# SELFiSSH.net
KiCad netlist of a schematic drawn in EAGLE
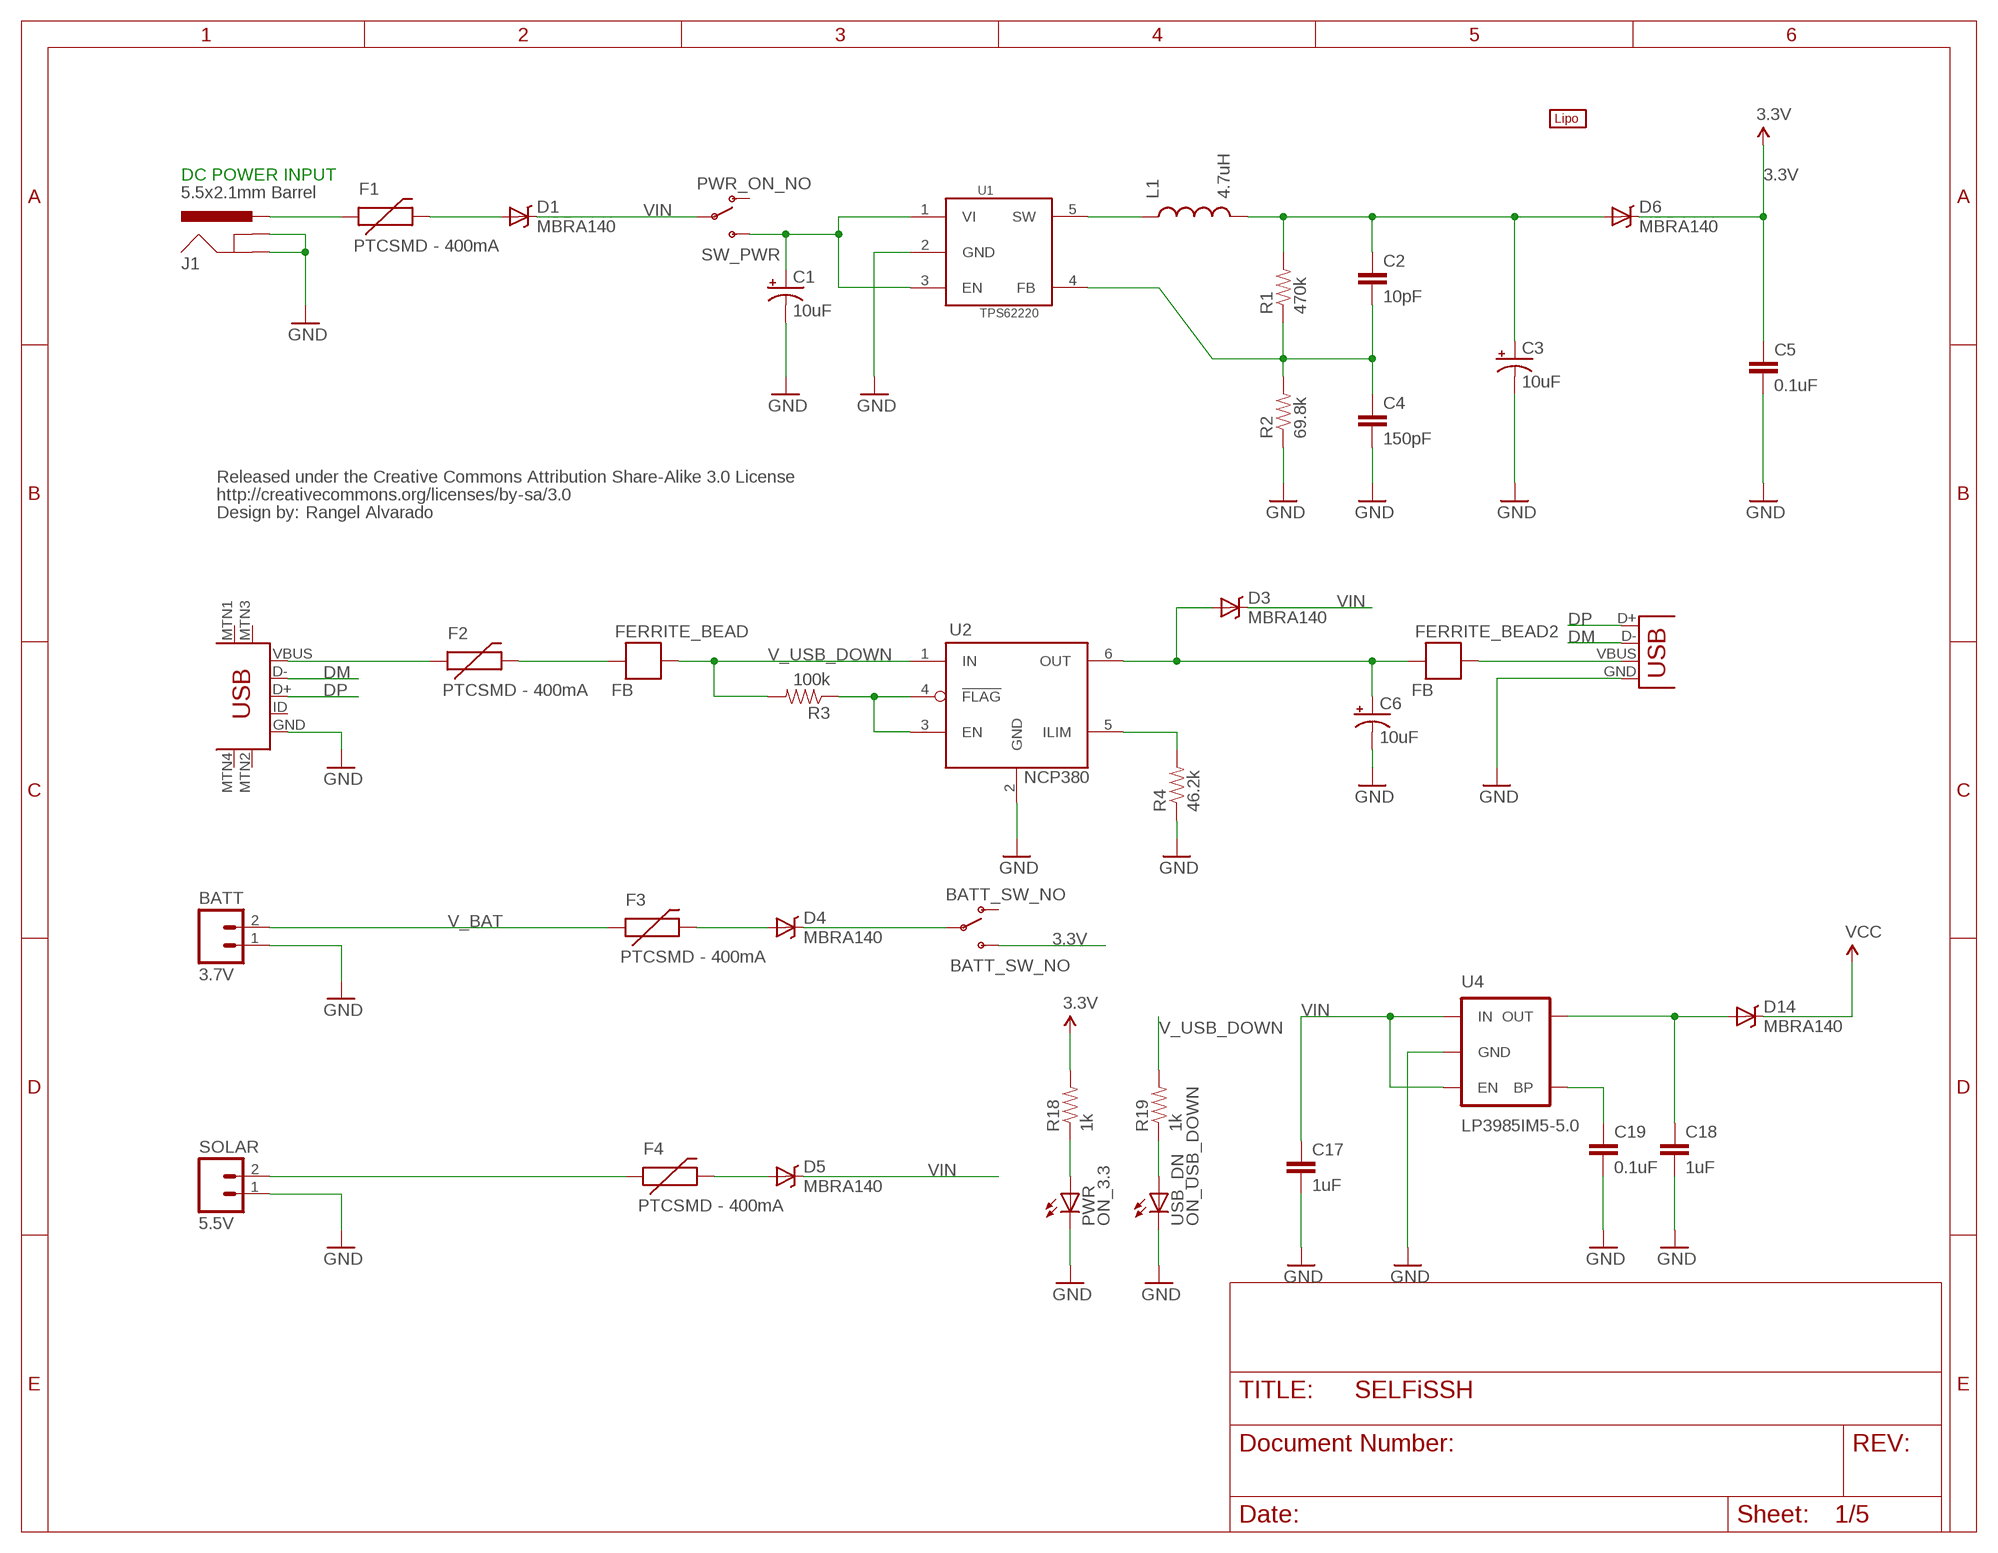
[diagram p0: schematic, sheet 1]
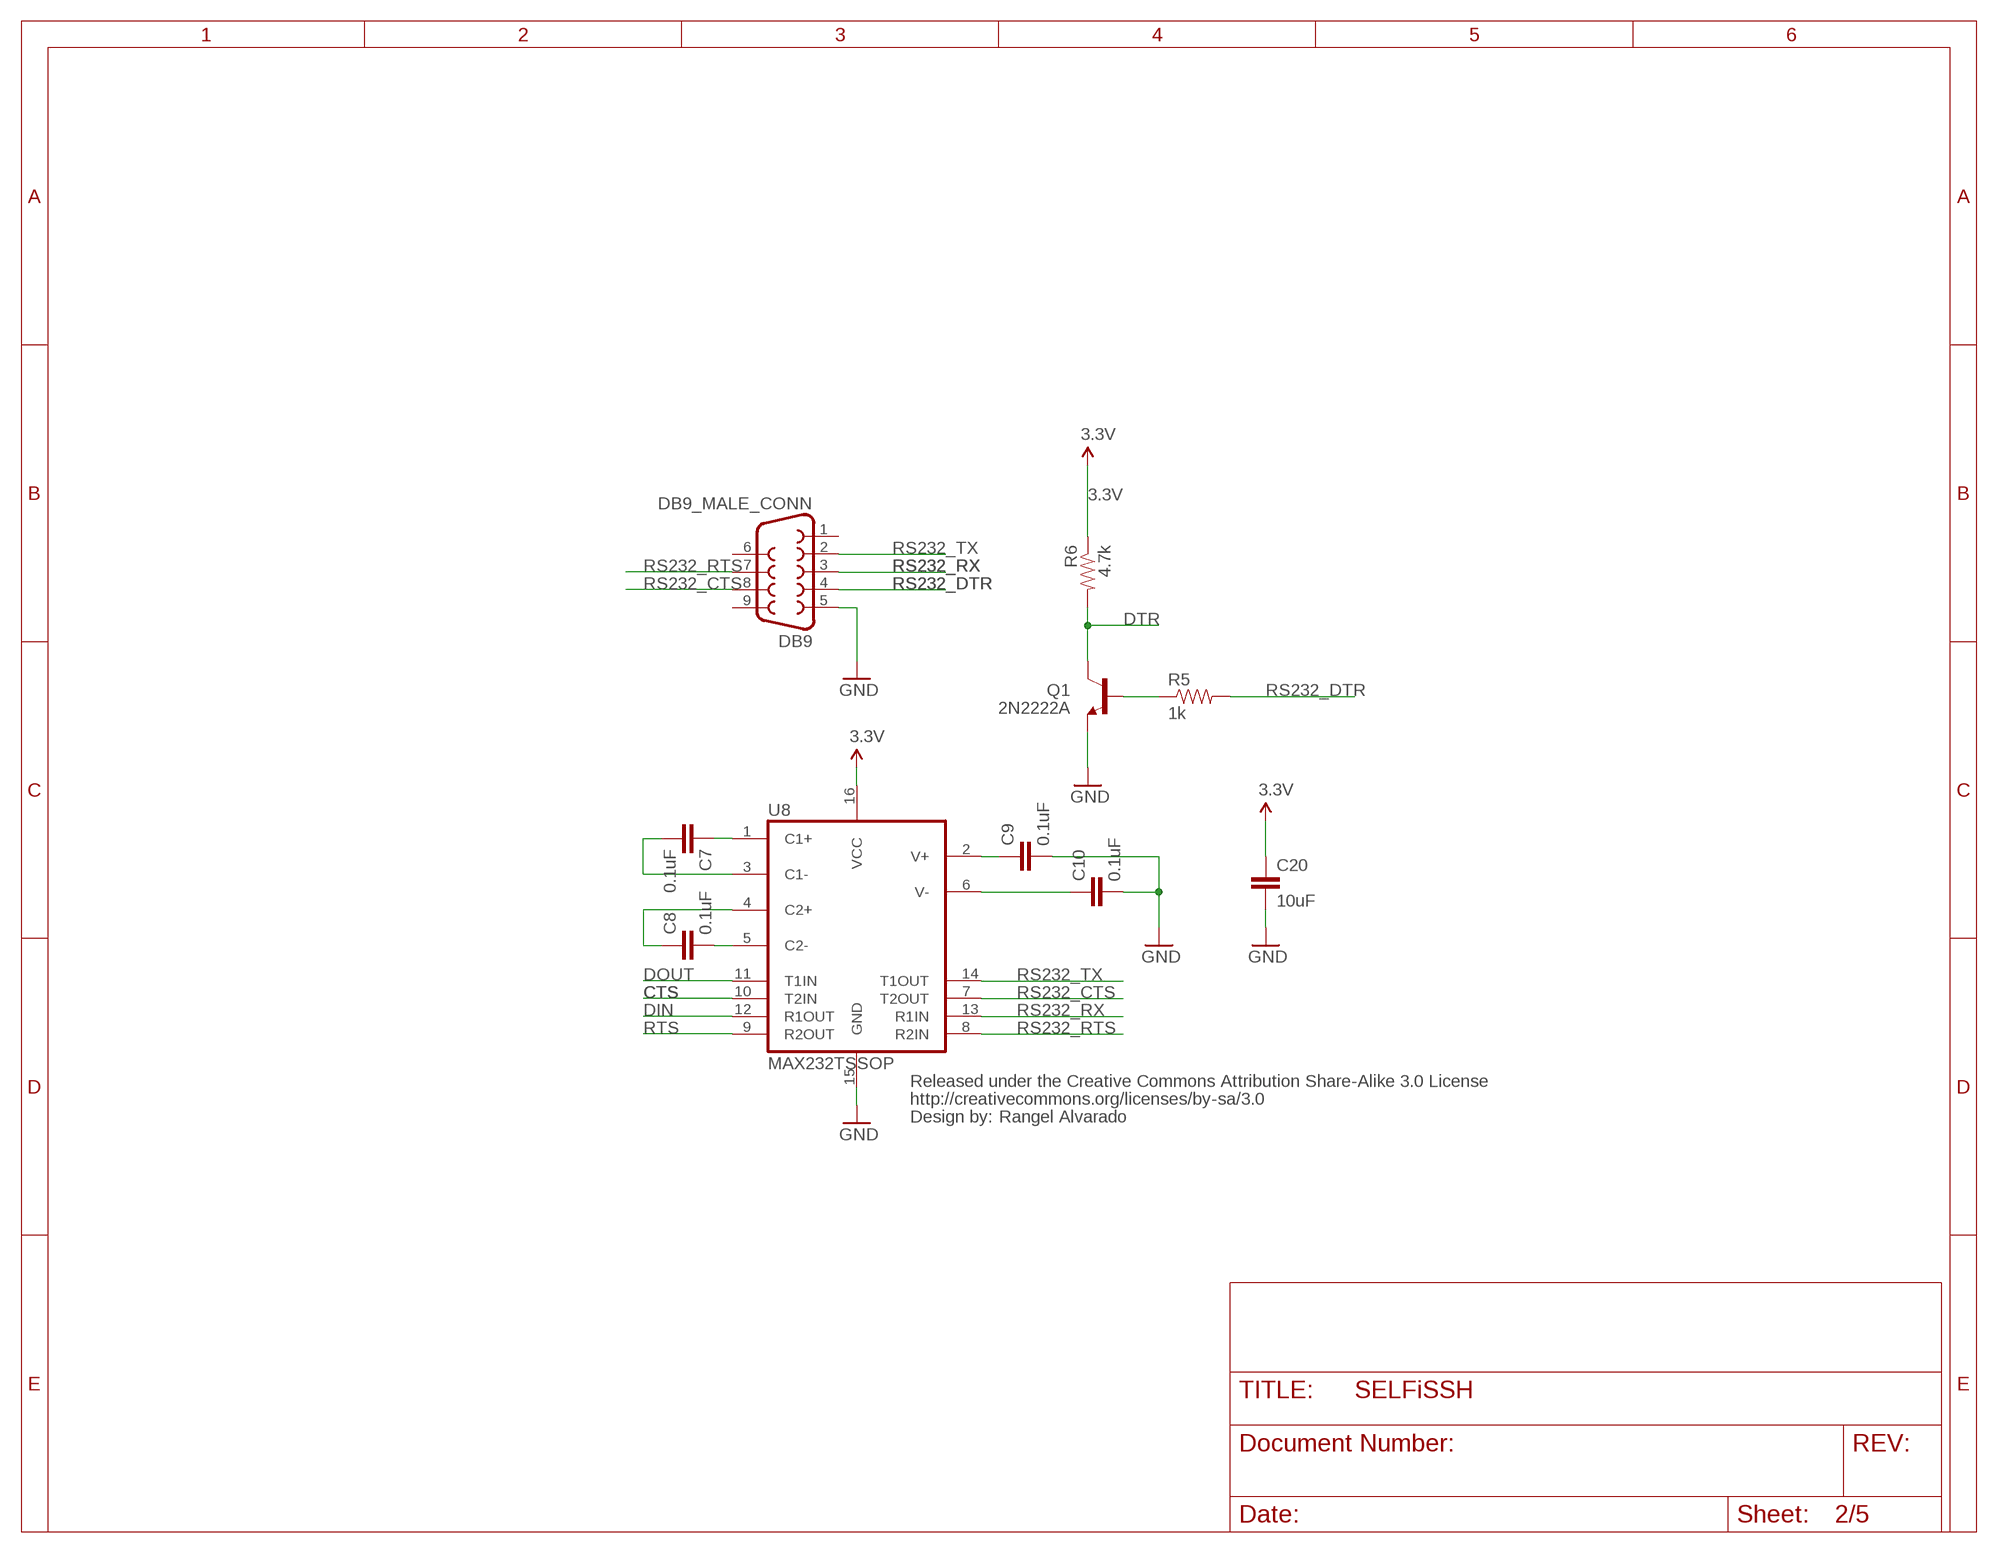
[diagram p1: schematic, sheet 2]
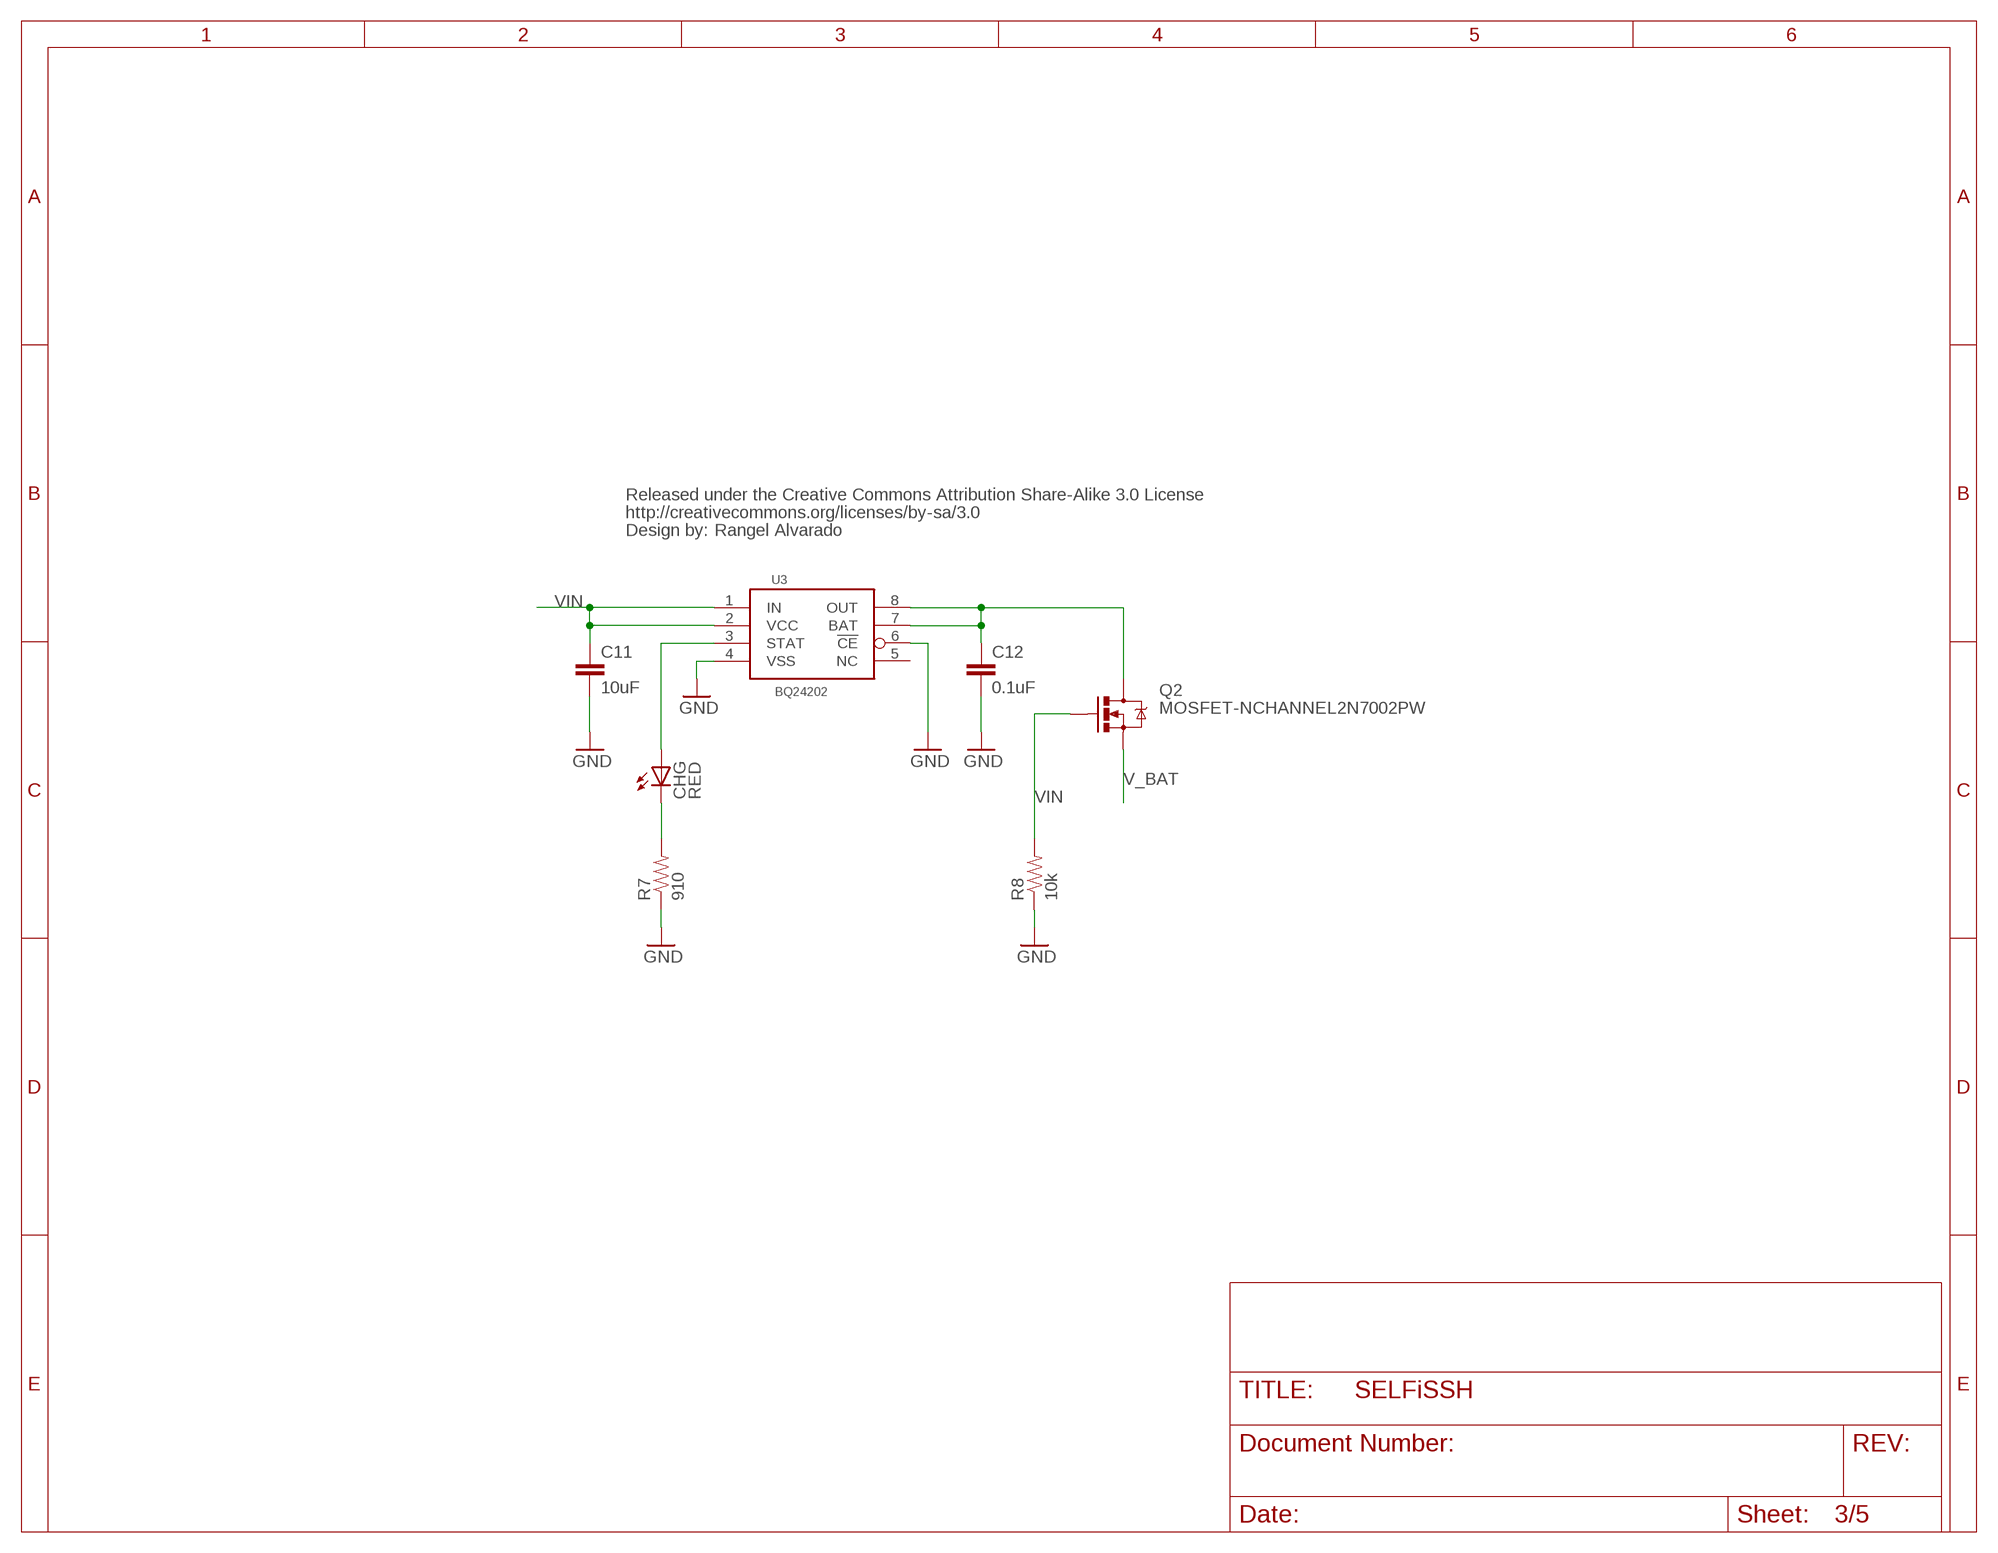
[diagram p2: schematic, sheet 3]
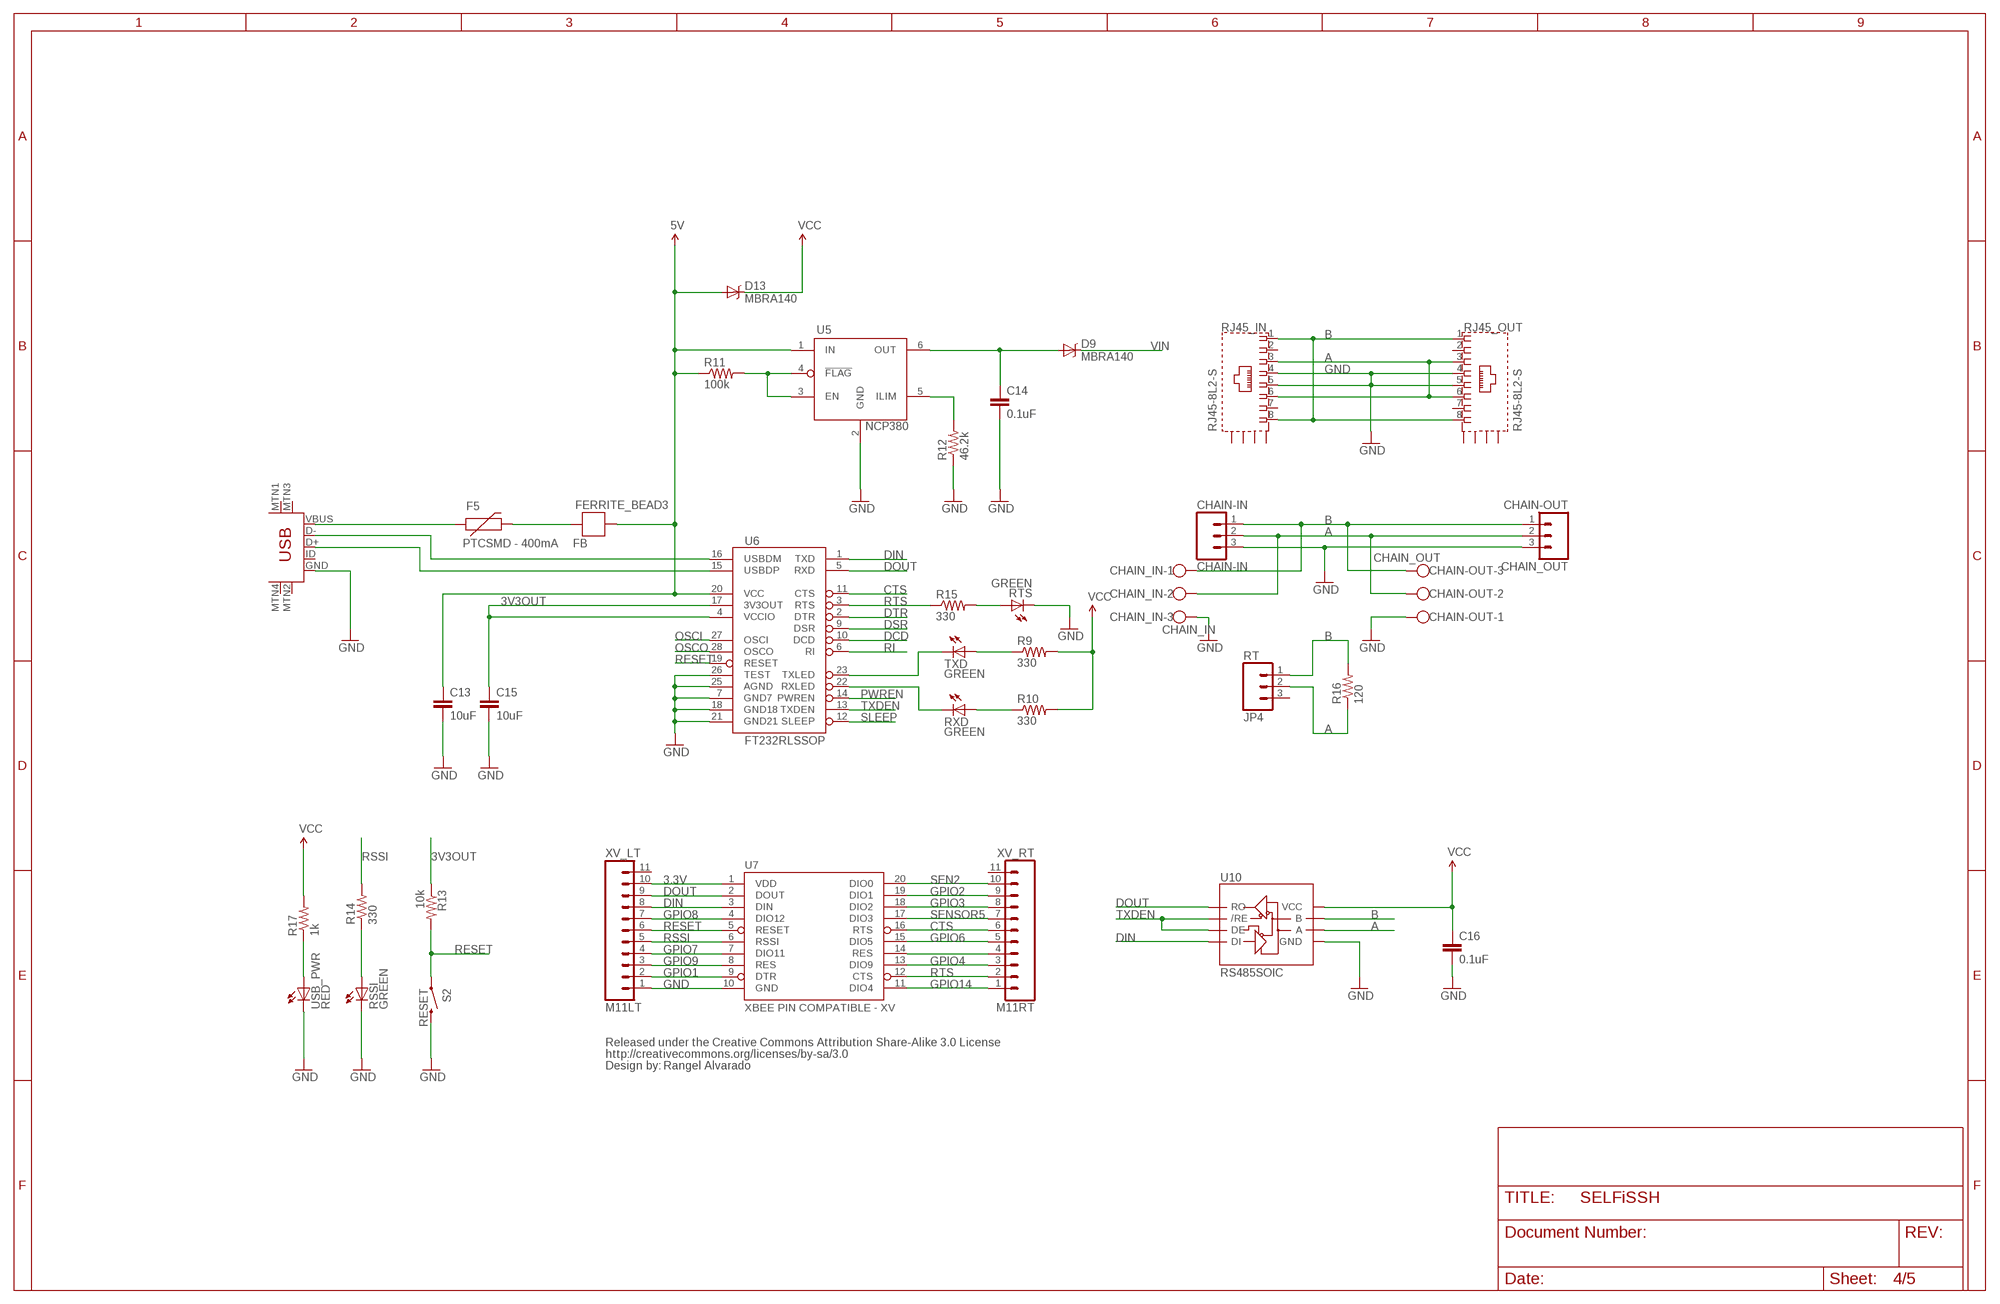
[diagram p3: schematic, sheet 4]
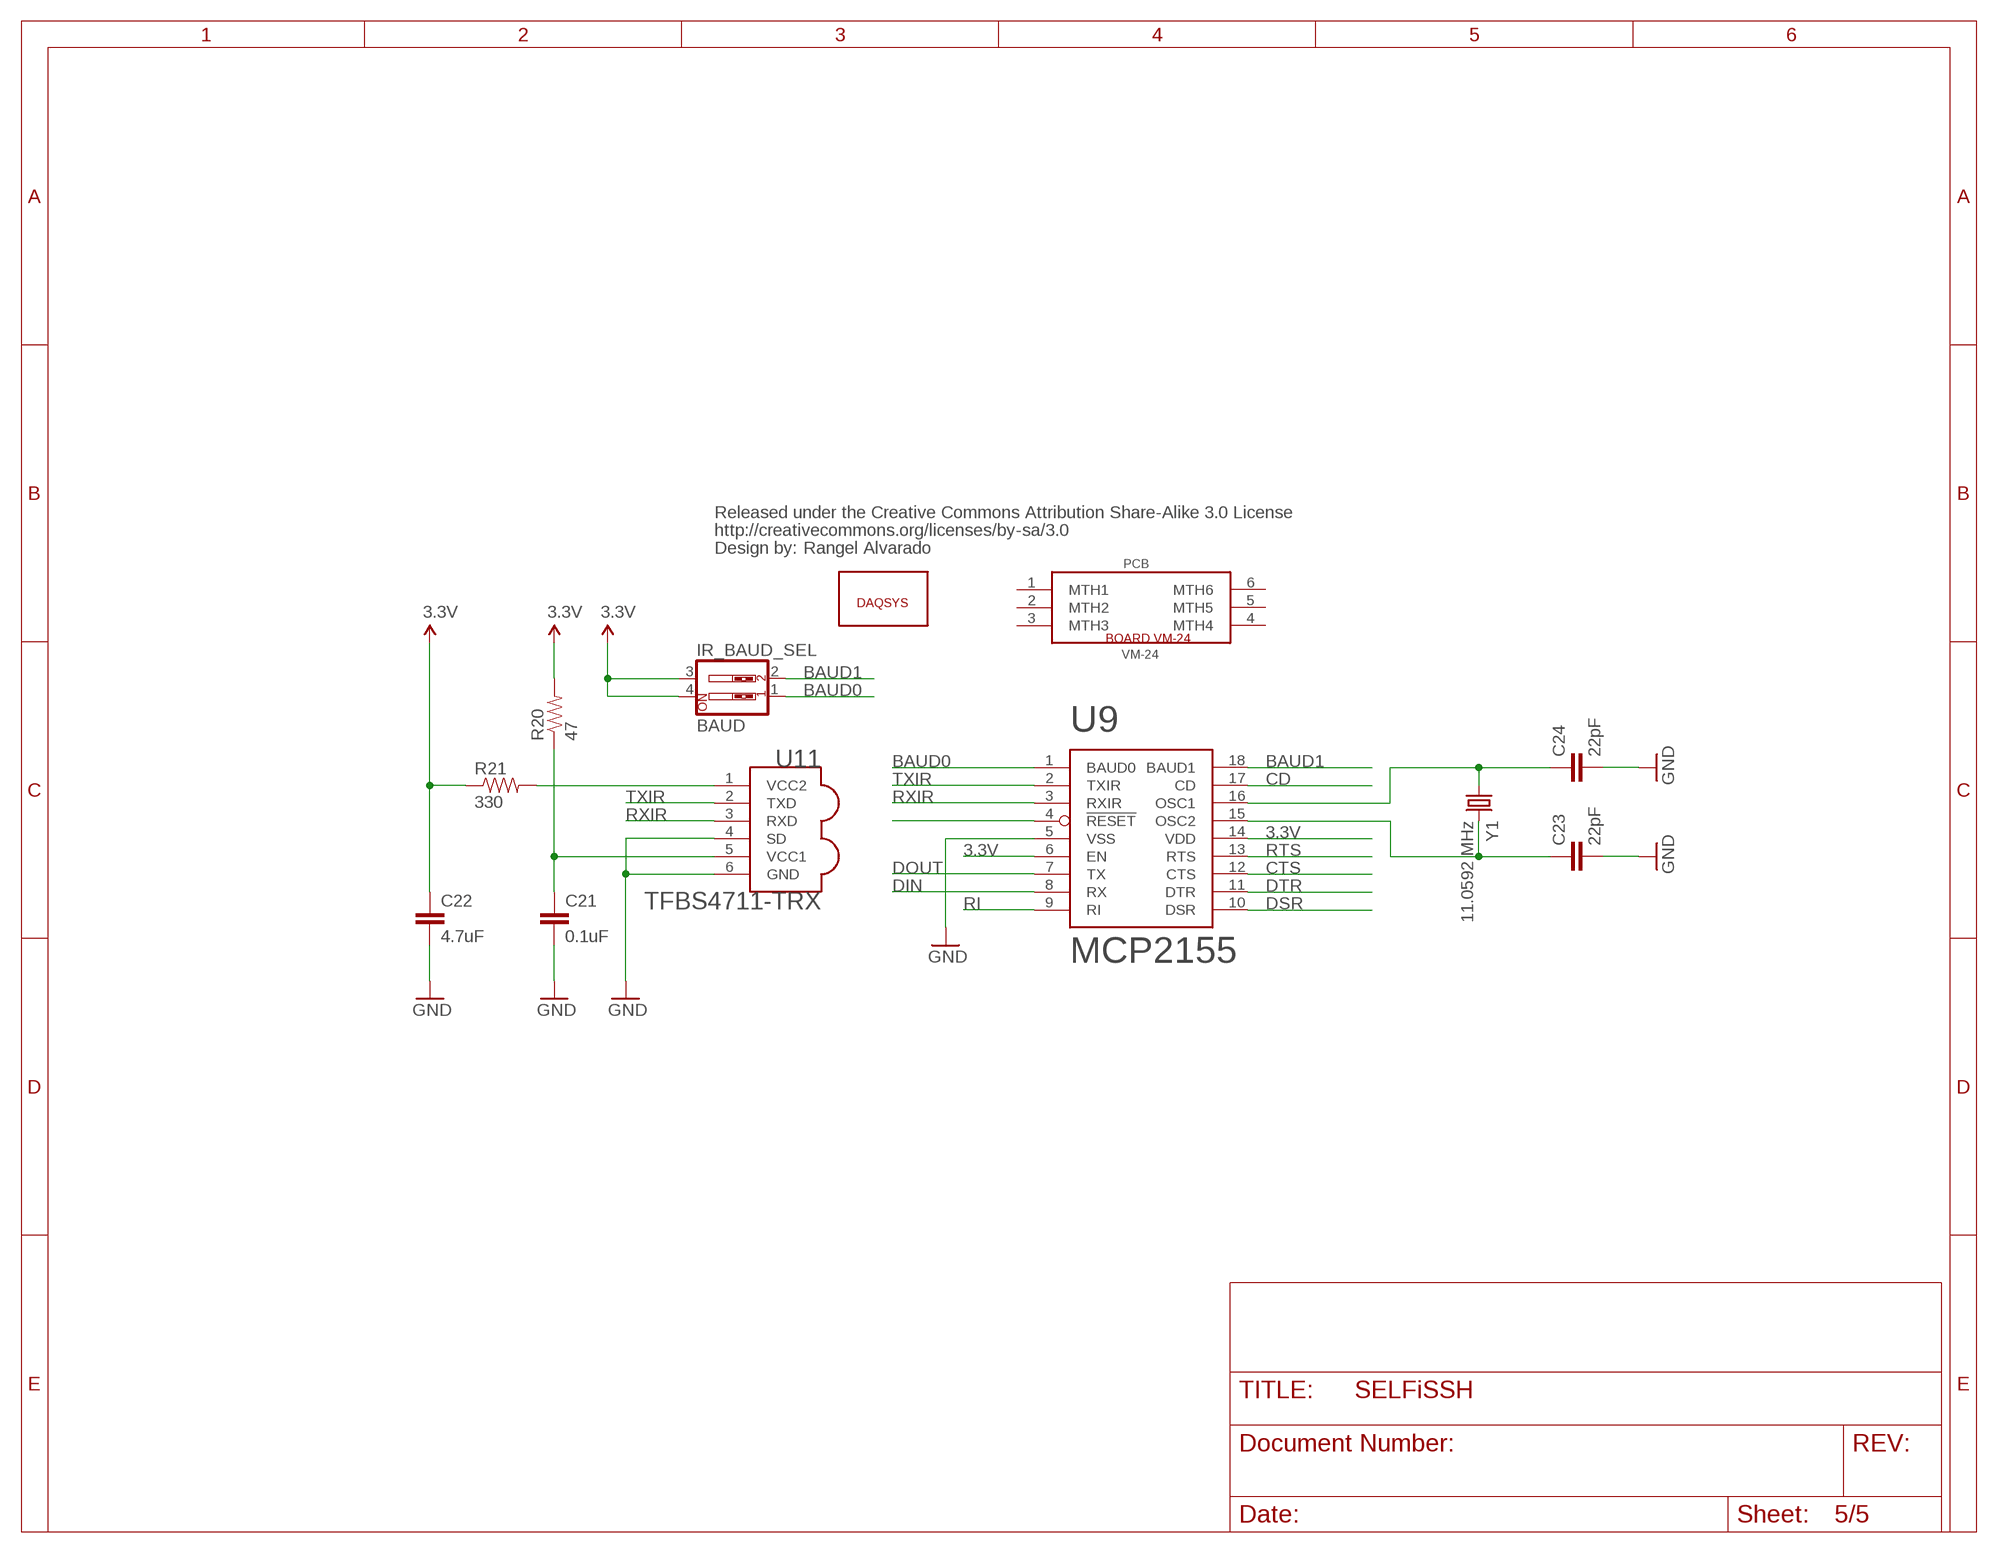
[diagram p4: schematic, sheet 5]

(export (version "E")
  (design (tool "Eeschema 10.0.6"))
  (components
    (comp (ref "C11")
      (value "10uF")
      (footprint "eagle-import:0805")
      (libsource (lib "eagle-import") (part "CAP0805"))
    )
    (comp (ref "C12")
      (value "0.1uF")
      (footprint "eagle-import:0805")
      (libsource (lib "eagle-import") (part "CAP0805"))
    )
    (comp (ref "CC_TEXT3")
      (value "CREATIVE_COMMONS")
      (footprint "eagle-import:CREATIVE_COMMONS")
      (libsource (lib "eagle-import") (part "CREATIVE_COMMONS"))
    )
    (comp (ref "CHG")
      (value "RED")
      (footprint "eagle-import:LED-1206")
      (libsource (lib "eagle-import") (part "LED-RED1206"))
    )
    (comp (ref "Q2")
      (value "MOSFET-NCHANNEL2N7002PW")
      (footprint "eagle-import:SOT323")
      (libsource (lib "eagle-import") (part "MOSFET-NCHANNEL2N7002PW"))
    )
    (comp (ref "R7")
      (value "910")
      (footprint "eagle-import:0805")
      (libsource (lib "eagle-import") (part "SparkFun-Resistors_RESISTOR0805-RES"))
    )
    (comp (ref "R8")
      (value "10k")
      (footprint "eagle-import:0805")
      (libsource (lib "eagle-import") (part "SparkFun-Resistors_RESISTOR0805-RES"))
    )
    (comp (ref "U3")
      (value "BQ24202")
      (footprint "eagle-import:MSOP-8")
      (libsource (lib "eagle-import") (part "BQ24202"))
    )
    (comp (ref "C7")
      (value "0.1uF")
      (footprint "eagle-import:0402-CAP")
      (libsource (lib "eagle-import") (part ".1UF-CER"))
    )
    (comp (ref "C8")
      (value "0.1uF")
      (footprint "eagle-import:0402-CAP")
      (libsource (lib "eagle-import") (part ".1UF-CER"))
    )
    (comp (ref "C9")
      (value "0.1uF")
      (footprint "eagle-import:0402-CAP")
      (libsource (lib "eagle-import") (part ".1UF-CER"))
    )
    (comp (ref "C10")
      (value "0.1uF")
      (footprint "eagle-import:0402-CAP")
      (libsource (lib "eagle-import") (part ".1UF-CER"))
    )
    (comp (ref "C20")
      (value "10uF")
      (footprint "eagle-import:0402-CAP")
      (libsource (lib "eagle-import") (part ".1UF-CER"))
    )
    (comp (ref "CC_TEXT2")
      (value "CREATIVE_COMMONS")
      (footprint "eagle-import:CREATIVE_COMMONS")
      (libsource (lib "eagle-import") (part "CREATIVE_COMMONS"))
    )
    (comp (ref "DB9_MALE_CONN")
      (value "DB9")
      (footprint "eagle-import:F09HP")
      (libsource (lib "eagle-import") (part "F09HP"))
    )
    (comp (ref "Q1")
      (value "2N2222A")
      (footprint "eagle-import:SOT23-3")
      (libsource (lib "eagle-import") (part "TRANSISTOR_NPNSOT23-3"))
    )
    (comp (ref "R5")
      (value "1k")
      (footprint "eagle-import:0402-RES")
      (libsource (lib "eagle-import") (part "RESISTOR0402-RES"))
    )
    (comp (ref "R6")
      (value "4.7k")
      (footprint "eagle-import:0402-RES")
      (libsource (lib "eagle-import") (part "RESISTOR0402-RES"))
    )
    (comp (ref "U8")
      (value "MAX232TSSOP")
      (footprint "eagle-import:TSSOP16")
      (libsource (lib "eagle-import") (part "MAX232TSSOP"))
    )
    (comp (ref "C13")
      (value "10uF")
      (footprint "eagle-import:0805")
      (libsource (lib "eagle-import") (part "CAP0805"))
    )
    (comp (ref "C14")
      (value "0.1uF")
      (footprint "eagle-import:0805")
      (libsource (lib "eagle-import") (part "CAP0805"))
    )
    (comp (ref "C15")
      (value "10uF")
      (footprint "eagle-import:0805")
      (libsource (lib "eagle-import") (part "CAP0805"))
    )
    (comp (ref "C16")
      (value "0.1uF")
      (footprint "eagle-import:0805")
      (libsource (lib "eagle-import") (part "CAP0805"))
    )
    (comp (ref "CC_TEXT4")
      (value "CREATIVE_COMMONS")
      (footprint "eagle-import:CREATIVE_COMMONS")
      (libsource (lib "eagle-import") (part "CREATIVE_COMMONS"))
    )
    (comp (ref "CHAIN-IN")
      (value "CHAIN-IN")
      (footprint "eagle-import:1X03_LONGPADS")
      (libsource (lib "eagle-import") (part "M03LONGPADS"))
    )
    (comp (ref "CHAIN-OUT")
      (value "CHAIN_OUT")
      (footprint "eagle-import:W237-103")
      (fields (field (name "MPN") "237-103"))
      (libsource (lib "eagle-import") (part "W237-103"))
    )
    (comp (ref "CHAIN_IN")
      (value "CHAIN_IN")
      (footprint "eagle-import:W237-103")
      (fields (field (name "MPN") "237-103"))
      (libsource (lib "eagle-import") (part "W237-103"))
    )
    (comp (ref "CHAIN_OUT")
      (value "CHAIN-OUT")
      (footprint "eagle-import:1X03_LONGPADS")
      (libsource (lib "eagle-import") (part "M03LONGPADS"))
    )
    (comp (ref "D9")
      (value "MBRA140")
      (footprint "eagle-import:SMA-DIODE")
      (libsource (lib "eagle-import") (part "MBRA140"))
    )
    (comp (ref "D13")
      (value "MBRA140")
      (footprint "eagle-import:SMA-DIODE")
      (fields (field (name "PROD_ID") "DIO-08053"))
      (libsource (lib "eagle-import") (part "MBRA140"))
    )
    (comp (ref "F5")
      (value "PTCSMD - 400mA")
      (footprint "eagle-import:PTC-1206")
      (libsource (lib "eagle-import") (part "PTCSMD"))
    )
    (comp (ref "FERRITE_BEAD3")
      (value "FB")
      (footprint "eagle-import:0603")
      (libsource (lib "eagle-import") (part "FB"))
    )
    (comp (ref "FTDI")
      (value "FTDI")
      (footprint "eagle-import:USB-MINIB")
      (libsource (lib "eagle-import") (part "USB-MINIB-5PIN"))
    )
    (comp (ref "JP4")
      (value "RT")
      (footprint "eagle-import:1X03_LONGPADS")
      (libsource (lib "eagle-import") (part "M03LONGPADS"))
    )
    (comp (ref "R9")
      (value "330")
      (footprint "eagle-import:0805")
      (libsource (lib "eagle-import") (part "RESISTOR0805-RES"))
    )
    (comp (ref "R10")
      (value "330")
      (footprint "eagle-import:0805")
      (libsource (lib "eagle-import") (part "RESISTOR0805-RES"))
    )
    (comp (ref "R11")
      (value "100k")
      (footprint "eagle-import:0805")
      (libsource (lib "eagle-import") (part "RESISTOR0805-RES"))
    )
    (comp (ref "R12")
      (value "46.2k")
      (footprint "eagle-import:0805")
      (libsource (lib "eagle-import") (part "RESISTOR0805-RES"))
    )
    (comp (ref "R13")
      (value "10k")
      (footprint "eagle-import:0805")
      (libsource (lib "eagle-import") (part "RESISTOR0805-RES"))
    )
    (comp (ref "R14")
      (value "330")
      (footprint "eagle-import:0805")
      (libsource (lib "eagle-import") (part "RESISTOR0805-RES"))
    )
    (comp (ref "R15")
      (value "330")
      (footprint "eagle-import:0805")
      (libsource (lib "eagle-import") (part "RESISTOR0805-RES"))
    )
    (comp (ref "R16")
      (value "120")
      (footprint "eagle-import:0805")
      (libsource (lib "eagle-import") (part "RESISTOR0805-RES"))
    )
    (comp (ref "R17")
      (value "1k")
      (footprint "eagle-import:0805")
      (libsource (lib "eagle-import") (part "RESISTOR0805-RES"))
    )
    (comp (ref "RJ45_IN")
      (value "RJ45-8L2-S")
      (footprint "eagle-import:RJ45-SHIELD2")
      (fields (field (name "MF") "TYCO ELECTRONICS"))
      (libsource (lib "eagle-import") (part "RJ452-S-8L"))
    )
    (comp (ref "RJ45_OUT")
      (value "RJ45-8L2-S")
      (footprint "eagle-import:RJ45-SHIELD2")
      (fields (field (name "MF") "TYCO ELECTRONICS"))
      (libsource (lib "eagle-import") (part "RJ452-S-8L"))
    )
    (comp (ref "RSSI")
      (value "GREEN")
      (footprint "eagle-import:LED-0603")
      (libsource (lib "eagle-import") (part "LED-GREEN0603"))
    )
    (comp (ref "RTS")
      (value "GREEN")
      (footprint "eagle-import:LED-0603")
      (libsource (lib "eagle-import") (part "LED0603"))
    )
    (comp (ref "RXD")
      (value "GREEN")
      (footprint "eagle-import:LED-0603")
      (libsource (lib "eagle-import") (part "LED0603"))
    )
    (comp (ref "S2")
      (value "RESET")
      (footprint "eagle-import:TACTILE_SWITCH_TALL")
      (libsource (lib "eagle-import") (part "SWITCH-MOMENTARY-2"))
    )
    (comp (ref "TXD")
      (value "GREEN")
      (footprint "eagle-import:LED-0603")
      (libsource (lib "eagle-import") (part "LED0603"))
    )
    (comp (ref "U5")
      (value "NCP380")
      (footprint "eagle-import:TSOP6")
      (libsource (lib "eagle-import") (part "NCP380NCP380VCC5"))
    )
    (comp (ref "U6")
      (value "FT232RLSSOP")
      (footprint "eagle-import:SSOP28DB")
      (libsource (lib "eagle-import") (part "FT232RLSSOP"))
    )
    (comp (ref "U7")
      (value "XBEE PIN COMPATIBLE - XV")
      (footprint "eagle-import:XBEE-SMD")
      (libsource (lib "eagle-import") (part "XBEE-1B3"))
    )
    (comp (ref "U10")
      (value "RS485SOIC")
      (footprint "eagle-import:SO08")
      (libsource (lib "eagle-import") (part "RS485SOIC"))
    )
    (comp (ref "USB_PWR")
      (value "RED")
      (footprint "eagle-import:LED-1206")
      (libsource (lib "eagle-import") (part "LED1206"))
    )
    (comp (ref "XV_LT")
      (value "M11LT")
      (footprint "eagle-import:1X11_LONGPADS")
      (libsource (lib "eagle-import") (part "M11LONGPADS"))
    )
    (comp (ref "XV_RT")
      (value "M11RT")
      (footprint "eagle-import:1X11_LONGPADS")
      (libsource (lib "eagle-import") (part "M11LONGPADS"))
    )
    (comp (ref "C21")
      (value "0.1uF")
      (footprint "eagle-import:0603-CAP")
      (libsource (lib "eagle-import") (part "CAP0603-CAP"))
    )
    (comp (ref "C22")
      (value "4.7uF")
      (footprint "eagle-import:0603-CAP")
      (libsource (lib "eagle-import") (part "CAP0603-CAP"))
    )
    (comp (ref "C23")
      (value "22pF")
      (footprint "eagle-import:0603-CAP")
      (libsource (lib "eagle-import") (part "CAP0603-CAP"))
    )
    (comp (ref "C24")
      (value "22pF")
      (footprint "eagle-import:0603-CAP")
      (libsource (lib "eagle-import") (part "CAP0603-CAP"))
    )
    (comp (ref "CC_TEXT5")
      (value "CREATIVE_COMMONS")
      (footprint "eagle-import:CREATIVE_COMMONS")
      (libsource (lib "eagle-import") (part "CREATIVE_COMMONS"))
    )
    (comp (ref "IR_BAUD_SEL")
      (value "BAUD")
      (footprint "eagle-import:DIPSWITCH-02")
      (libsource (lib "eagle-import") (part "SW_DIP-2"))
    )
    (comp (ref "PCB")
      (value "VM-24")
      (footprint "eagle-import:VM-24")
      (libsource (lib "eagle-import") (part "VM-24"))
    )
    (comp (ref "R20")
      (value "47")
      (footprint "eagle-import:0603-RES")
      (libsource (lib "eagle-import") (part "SparkFun-Resistors_RESISTOR0603-RES"))
    )
    (comp (ref "R21")
      (value "330")
      (footprint "eagle-import:0603-RES")
      (libsource (lib "eagle-import") (part "SparkFun-Resistors_RESISTOR0603-RES"))
    )
    (comp (ref "U$1")
      (value "DAQSYS")
      (footprint "eagle-import:DAQSYS")
      (libsource (lib "eagle-import") (part "DAQSYS"))
    )
    (comp (ref "U9")
      (value "MCP2155")
      (footprint "eagle-import:SOIC18-W")
      (libsource (lib "eagle-import") (part "MCP2155"))
    )
    (comp (ref "U11")
      (value "TFBS4711-TRX")
      (footprint "eagle-import:SMD-6")
      (libsource (lib "eagle-import") (part "TFBS4711-TRX"))
    )
    (comp (ref "Y1")
      (value "11.0592 MHz")
      (footprint "eagle-import:CRYSTAL-SMD-5X3")
      (libsource (lib "eagle-import") (part "CRYSTAL5X3"))
    )
    (comp (ref "BATT")
      (value "3.7V")
      (footprint "eagle-import:JST-2-PTH")
      (libsource (lib "eagle-import") (part "M02JST-PTH-2"))
    )
    (comp (ref "BATT_SW_NO")
      (value "BATT_SW_NO")
      (footprint "eagle-import:SWITCH-SPDT-SMD")
      (libsource (lib "eagle-import") (part "SWITCH-SPDTSMD2"))
    )
    (comp (ref "C1")
      (value "10uF")
      (footprint "eagle-import:EIA3216")
      (libsource (lib "eagle-import") (part "10UF-16V-10%(TANT)"))
    )
    (comp (ref "C2")
      (value "10pF")
      (footprint "eagle-import:0805")
      (libsource (lib "eagle-import") (part "1UF-25V-10%(0805)"))
    )
    (comp (ref "C3")
      (value "10uF")
      (footprint "eagle-import:EIA3216")
      (libsource (lib "eagle-import") (part "10UF-16V-10%(TANT)"))
    )
    (comp (ref "C4")
      (value "150pF")
      (footprint "eagle-import:0805")
      (libsource (lib "eagle-import") (part "1UF-25V-10%(0805)"))
    )
    (comp (ref "C5")
      (value "0.1uF")
      (footprint "eagle-import:0805")
      (libsource (lib "eagle-import") (part "1UF-25V-10%(0805)"))
    )
    (comp (ref "C6")
      (value "10uF")
      (footprint "eagle-import:EIA3216")
      (libsource (lib "eagle-import") (part "10UF-16V-10%(TANT)"))
    )
    (comp (ref "C17")
      (value "1uF")
      (footprint "eagle-import:0805")
      (fields (field (name "PROD_ID") "CAP-08064"))
      (libsource (lib "eagle-import") (part "1UF-25V-10%(0805)"))
    )
    (comp (ref "C18")
      (value "1uF")
      (footprint "eagle-import:0805")
      (fields (field (name "PROD_ID") "CAP-08064"))
      (libsource (lib "eagle-import") (part "1UF-25V-10%(0805)"))
    )
    (comp (ref "C19")
      (value "0.1uF")
      (footprint "eagle-import:0805")
      (fields (field (name "PROD_ID") "CAP-08064"))
      (libsource (lib "eagle-import") (part "1UF-25V-10%(0805)"))
    )
    (comp (ref "CC_TEXT1")
      (value "CREATIVE_COMMONS")
      (footprint "eagle-import:CREATIVE_COMMONS")
      (libsource (lib "eagle-import") (part "CREATIVE_COMMONS"))
    )
    (comp (ref "D1")
      (value "MBRA140")
      (footprint "eagle-import:SMA-DIODE")
      (libsource (lib "eagle-import") (part "MBRA140"))
    )
    (comp (ref "D3")
      (value "MBRA140")
      (footprint "eagle-import:SMA-DIODE")
      (libsource (lib "eagle-import") (part "MBRA140"))
    )
    (comp (ref "D4")
      (value "MBRA140")
      (footprint "eagle-import:SMA-DIODE")
      (libsource (lib "eagle-import") (part "MBRA140"))
    )
    (comp (ref "D5")
      (value "MBRA140")
      (footprint "eagle-import:SMA-DIODE")
      (libsource (lib "eagle-import") (part "MBRA140"))
    )
    (comp (ref "D6")
      (value "MBRA140")
      (footprint "eagle-import:SMA-DIODE")
      (libsource (lib "eagle-import") (part "MBRA140"))
    )
    (comp (ref "D14")
      (value "MBRA140")
      (footprint "eagle-import:SMA-DIODE")
      (fields (field (name "PROD_ID") "DIO-08053"))
      (libsource (lib "eagle-import") (part "MBRA140"))
    )
    (comp (ref "F1")
      (value "PTCSMD - 400mA")
      (footprint "eagle-import:PTC-1206")
      (libsource (lib "eagle-import") (part "PTCSMD"))
    )
    (comp (ref "F2")
      (value "PTCSMD - 400mA")
      (footprint "eagle-import:PTC-1206")
      (libsource (lib "eagle-import") (part "PTCSMD"))
    )
    (comp (ref "F3")
      (value "PTCSMD - 400mA")
      (footprint "eagle-import:PTC-1206")
      (libsource (lib "eagle-import") (part "PTCSMD"))
    )
    (comp (ref "F4")
      (value "PTCSMD - 400mA")
      (footprint "eagle-import:PTC-1206")
      (libsource (lib "eagle-import") (part "PTCSMD"))
    )
    (comp (ref "FERRITE_BEAD")
      (value "FB")
      (footprint "eagle-import:0603")
      (libsource (lib "eagle-import") (part "FB"))
    )
    (comp (ref "FERRITE_BEAD2")
      (value "FB")
      (footprint "eagle-import:0603")
      (libsource (lib "eagle-import") (part "FB"))
    )
    (comp (ref "J1")
      (value "5.5x2.1mm Barrel")
      (footprint "eagle-import:POWER_JACK_SMD")
      (libsource (lib "eagle-import") (part "POWER_JACKSMD"))
    )
    (comp (ref "L1")
      (value "4.7uH")
      (footprint "eagle-import:0805")
      (libsource (lib "eagle-import") (part "INDUCTOR0805"))
    )
    (comp (ref "PWR")
      (value "ON_3.3")
      (footprint "eagle-import:LED-0603")
      (libsource (lib "eagle-import") (part "LED0603"))
    )
    (comp (ref "R1")
      (value "470k")
      (footprint "eagle-import:0603-RES")
      (libsource (lib "eagle-import") (part "RESISTOR0603-RES"))
    )
    (comp (ref "R2")
      (value "69.8k")
      (footprint "eagle-import:0603-RES")
      (libsource (lib "eagle-import") (part "RESISTOR0603-RES"))
    )
    (comp (ref "R3")
      (value "100k")
      (footprint "eagle-import:0603-RES")
      (libsource (lib "eagle-import") (part "RESISTOR0603-RES"))
    )
    (comp (ref "R4")
      (value "46.2k")
      (footprint "eagle-import:0603-RES")
      (libsource (lib "eagle-import") (part "RESISTOR0603-RES"))
    )
    (comp (ref "R18")
      (value "1k")
      (footprint "eagle-import:0603-RES")
      (libsource (lib "eagle-import") (part "RESISTOR0603-RES"))
    )
    (comp (ref "R19")
      (value "1k")
      (footprint "eagle-import:0603-RES")
      (libsource (lib "eagle-import") (part "RESISTOR0603-RES"))
    )
    (comp (ref "SOLAR")
      (value "5.5V")
      (footprint "eagle-import:JST-2-PTH")
      (libsource (lib "eagle-import") (part "M02JST-PTH-2"))
    )
    (comp (ref "SW_PWR")
      (value "PWR_ON_NO")
      (footprint "eagle-import:SWITCH-SPDT-SMD")
      (libsource (lib "eagle-import") (part "SWITCH-SPDTSMD2"))
    )
    (comp (ref "U$7")
      (value "LIPO-OUTLINE1100")
      (footprint "eagle-import:LIPO-1100")
      (libsource (lib "eagle-import") (part "LIPO-OUTLINE1100"))
    )
    (comp (ref "U1")
      (value "TPS62220")
      (footprint "eagle-import:TSOT-23-5")
      (libsource (lib "eagle-import") (part "TPS62220"))
    )
    (comp (ref "U2")
      (value "NCP380")
      (footprint "eagle-import:TSOP6")
      (libsource (lib "eagle-import") (part "NCP380NCP380VCC5"))
    )
    (comp (ref "U4")
      (value "LP3985IM5-5.0")
      (footprint "eagle-import:SOT23-5")
      (libsource (lib "eagle-import") (part "V_REG_LDOSMD"))
    )
    (comp (ref "USB_DN")
      (value "ON_USB_DOWN")
      (footprint "eagle-import:LED-0603")
      (libsource (lib "eagle-import") (part "LED0603"))
    )
    (comp (ref "USB_IN")
      (value "USB_IN")
      (footprint "eagle-import:USB-MINIB")
      (libsource (lib "eagle-import") (part "USB-MINIB-5PIN"))
    )
    (comp (ref "USB_OUT")
      (value "USB_OUT")
      (footprint "eagle-import:USB-A-S-SILK-FEMALE")
      (libsource (lib "eagle-import") (part "USB_"))
    )
  )
  (nets
    (net (code "1") (name "3.3V") (class "Default")
      (node (ref "BATT_SW_NO") (pin "3") (pinfunction "S_3") (pintype "passive"))
      (node (ref "C20") (pin "1") (pinfunction "1_1") (pintype "passive"))
      (node (ref "C22") (pin "1") (pinfunction "1_1") (pintype "passive"))
      (node (ref "C5") (pin "1") (pinfunction "1_1") (pintype "passive"))
      (node (ref "D6") (pin "C") (pinfunction "C_C") (pintype "passive"))
      (node (ref "IR_BAUD_SEL") (pin "3") (pinfunction "3_3") (pintype "passive"))
      (node (ref "IR_BAUD_SEL") (pin "4") (pinfunction "4_4") (pintype "passive"))
      (node (ref "R18") (pin "2") (pinfunction "2_2") (pintype "passive"))
      (node (ref "R20") (pin "2") (pinfunction "2_2") (pintype "passive"))
      (node (ref "R21") (pin "1") (pinfunction "1_1") (pintype "passive"))
      (node (ref "R6") (pin "1") (pinfunction "1_1") (pintype "passive"))
      (node (ref "U7") (pin "1") (pinfunction "VDD_1") (pintype "power_in"))
      (node (ref "U8") (pin "16") (pinfunction "VCC_16") (pintype "bidirectional"))
      (node (ref "U9") (pin "14") (pinfunction "VDD_14") (pintype "bidirectional"))
      (node (ref "U9") (pin "6") (pinfunction "EN_6") (pintype "bidirectional"))
      (node (ref "XV_LT") (pin "10") (pinfunction "10_10") (pintype "passive"))
    )
    (net (code "2") (name "3V3OUT") (class "Default")
      (node (ref "C15") (pin "1") (pinfunction "1_1") (pintype "passive"))
      (node (ref "R13") (pin "1") (pinfunction "1_1") (pintype "passive"))
      (node (ref "U6") (pin "17") (pinfunction "3V3OUT_17") (pintype "output"))
      (node (ref "U6") (pin "4") (pinfunction "VCCIO_4") (pintype "power_in"))
    )
    (net (code "3") (name "5V") (class "Default")
      (node (ref "C13") (pin "1") (pinfunction "1_1") (pintype "passive"))
      (node (ref "D13") (pin "A") (pinfunction "A_A") (pintype "passive"))
      (node (ref "FERRITE_BEAD3") (pin "1") (pinfunction "P$1_1") (pintype "bidirectional"))
      (node (ref "R11") (pin "1") (pinfunction "1_1") (pintype "passive"))
      (node (ref "U5") (pin "1") (pinfunction "IN_1") (pintype "bidirectional"))
      (node (ref "U6") (pin "20") (pinfunction "VCC_20") (pintype "power_in"))
    )
    (net (code "4") (name "A") (class "Default")
      (node (ref "CHAIN-IN") (pin "2") (pinfunction "2_2") (pintype "passive"))
      (node (ref "CHAIN-OUT") (pin "2") (pinfunction "KL_2") (pintype "passive"))
      (node (ref "CHAIN_IN") (pin "2") (pinfunction "KL_2") (pintype "passive"))
      (node (ref "CHAIN_OUT") (pin "2") (pinfunction "2_2") (pintype "passive"))
      (node (ref "JP4") (pin "2") (pinfunction "2_2") (pintype "passive"))
      (node (ref "R16") (pin "1") (pinfunction "1_1") (pintype "passive"))
      (node (ref "RJ45_IN") (pin "3") (pinfunction "3_3") (pintype "passive"))
      (node (ref "RJ45_IN") (pin "6") (pinfunction "6_6") (pintype "passive"))
      (node (ref "RJ45_OUT") (pin "3") (pinfunction "3_3") (pintype "passive"))
      (node (ref "RJ45_OUT") (pin "6") (pinfunction "6_6") (pintype "passive"))
      (node (ref "U10") (pin "6") (pinfunction "A_6") (pintype "bidirectional"))
    )
    (net (code "5") (name "B") (class "Default")
      (node (ref "CHAIN-IN") (pin "1") (pinfunction "1_1") (pintype "passive"))
      (node (ref "CHAIN-OUT") (pin "3") (pinfunction "KL_3") (pintype "passive"))
      (node (ref "CHAIN_IN") (pin "1") (pinfunction "KL_1") (pintype "passive"))
      (node (ref "CHAIN_OUT") (pin "1") (pinfunction "1_1") (pintype "passive"))
      (node (ref "JP4") (pin "1") (pinfunction "1_1") (pintype "passive"))
      (node (ref "R16") (pin "2") (pinfunction "2_2") (pintype "passive"))
      (node (ref "RJ45_IN") (pin "1") (pinfunction "1_1") (pintype "passive"))
      (node (ref "RJ45_IN") (pin "8") (pinfunction "8_8") (pintype "passive"))
      (node (ref "RJ45_OUT") (pin "1") (pinfunction "1_1") (pintype "passive"))
      (node (ref "RJ45_OUT") (pin "8") (pinfunction "8_8") (pintype "passive"))
      (node (ref "U10") (pin "7") (pinfunction "B_7") (pintype "bidirectional"))
    )
    (net (code "6") (name "BAUD0") (class "Default")
      (node (ref "IR_BAUD_SEL") (pin "1") (pinfunction "1_1") (pintype "passive"))
      (node (ref "U9") (pin "1") (pinfunction "BAUD0_1") (pintype "bidirectional"))
    )
    (net (code "7") (name "BAUD1") (class "Default")
      (node (ref "IR_BAUD_SEL") (pin "2") (pinfunction "2_2") (pintype "passive"))
      (node (ref "U9") (pin "18") (pinfunction "BAUD1_18") (pintype "bidirectional"))
    )
    (net (code "8") (name "CD") (class "Default")
      (node (ref "U9") (pin "17") (pinfunction "CD_17") (pintype "bidirectional"))
    )
    (net (code "9") (name "CTS") (class "Default")
      (node (ref "U6") (pin "11") (pinfunction "CTS_11") (pintype "input"))
      (node (ref "U7") (pin "16") (pinfunction "RTS_16") (pintype "input"))
      (node (ref "U8") (pin "10") (pinfunction "T2IN_10") (pintype "input"))
      (node (ref "U9") (pin "12") (pinfunction "CTS_12") (pintype "bidirectional"))
      (node (ref "XV_RT") (pin "6") (pinfunction "6_6") (pintype "passive"))
    )
    (net (code "10") (name "DCD") (class "Default")
      (node (ref "U6") (pin "10") (pinfunction "DCD_10") (pintype "input"))
    )
    (net (code "11") (name "DIN") (class "Default")
      (node (ref "U10") (pin "4") (pinfunction "DI_4") (pintype "bidirectional"))
      (node (ref "U6") (pin "1") (pinfunction "TXD_1") (pintype "output"))
      (node (ref "U7") (pin "3") (pinfunction "DIN_3") (pintype "input"))
      (node (ref "U8") (pin "12") (pinfunction "R1OUT_12") (pintype "output"))
      (node (ref "U9") (pin "8") (pinfunction "RX_8") (pintype "bidirectional"))
      (node (ref "XV_LT") (pin "8") (pinfunction "8_8") (pintype "passive"))
    )
    (net (code "12") (name "DM") (class "Default")
      (node (ref "USB_IN") (pin "D-") (pinfunction "D-_D-") (pintype "bidirectional"))
      (node (ref "USB_OUT") (pin "D-") (pinfunction "D-_D-") (pintype "bidirectional"))
    )
    (net (code "13") (name "DOUT") (class "Default")
      (node (ref "U10") (pin "1") (pinfunction "RO_1") (pintype "bidirectional"))
      (node (ref "U6") (pin "5") (pinfunction "RXD_5") (pintype "input"))
      (node (ref "U7") (pin "2") (pinfunction "DOUT_2") (pintype "output"))
      (node (ref "U8") (pin "11") (pinfunction "T1IN_11") (pintype "input"))
      (node (ref "U9") (pin "7") (pinfunction "TX_7") (pintype "bidirectional"))
      (node (ref "XV_LT") (pin "9") (pinfunction "9_9") (pintype "passive"))
    )
    (net (code "14") (name "DP") (class "Default")
      (node (ref "USB_IN") (pin "D+") (pinfunction "D+_D+") (pintype "bidirectional"))
      (node (ref "USB_OUT") (pin "D+") (pinfunction "D+_D+") (pintype "bidirectional"))
    )
    (net (code "15") (name "DSR") (class "Default")
      (node (ref "U6") (pin "9") (pinfunction "DSR_9") (pintype "input"))
      (node (ref "U9") (pin "10") (pinfunction "DSR_10") (pintype "bidirectional"))
    )
    (net (code "16") (name "DTR") (class "Default")
      (node (ref "Q1") (pin "3") (pinfunction "C_3") (pintype "passive"))
      (node (ref "R6") (pin "2") (pinfunction "2_2") (pintype "passive"))
      (node (ref "U6") (pin "2") (pinfunction "DTR_2") (pintype "output"))
      (node (ref "U9") (pin "11") (pinfunction "DTR_11") (pintype "bidirectional"))
    )
    (net (code "17") (name "GND") (class "Default")
      (node (ref "BATT") (pin "1") (pinfunction "1_1") (pintype "passive"))
      (node (ref "C1") (pin "C") (pinfunction "-_C") (pintype "passive"))
      (node (ref "C10") (pin "2") (pinfunction "2_2") (pintype "passive"))
      (node (ref "C11") (pin "2") (pinfunction "2_2") (pintype "passive"))
      (node (ref "C12") (pin "2") (pinfunction "2_2") (pintype "passive"))
      (node (ref "C13") (pin "2") (pinfunction "2_2") (pintype "passive"))
      (node (ref "C14") (pin "2") (pinfunction "2_2") (pintype "passive"))
      (node (ref "C15") (pin "2") (pinfunction "2_2") (pintype "passive"))
      (node (ref "C16") (pin "2") (pinfunction "2_2") (pintype "passive"))
      (node (ref "C17") (pin "2") (pinfunction "2_2") (pintype "passive"))
      (node (ref "C18") (pin "2") (pinfunction "2_2") (pintype "passive"))
      (node (ref "C19") (pin "2") (pinfunction "2_2") (pintype "passive"))
      (node (ref "C20") (pin "2") (pinfunction "2_2") (pintype "passive"))
      (node (ref "C21") (pin "2") (pinfunction "2_2") (pintype "passive"))
      (node (ref "C22") (pin "2") (pinfunction "2_2") (pintype "passive"))
      (node (ref "C23") (pin "2") (pinfunction "2_2") (pintype "passive"))
      (node (ref "C24") (pin "2") (pinfunction "2_2") (pintype "passive"))
      (node (ref "C3") (pin "C") (pinfunction "-_C") (pintype "passive"))
      (node (ref "C4") (pin "2") (pinfunction "2_2") (pintype "passive"))
      (node (ref "C5") (pin "2") (pinfunction "2_2") (pintype "passive"))
      (node (ref "C6") (pin "C") (pinfunction "-_C") (pintype "passive"))
      (node (ref "C9") (pin "2") (pinfunction "2_2") (pintype "passive"))
      (node (ref "CHAIN-IN") (pin "3") (pinfunction "3_3") (pintype "passive"))
      (node (ref "CHAIN-OUT") (pin "1") (pinfunction "KL_1") (pintype "passive"))
      (node (ref "CHAIN_IN") (pin "3") (pinfunction "KL_3") (pintype "passive"))
      (node (ref "CHAIN_OUT") (pin "3") (pinfunction "3_3") (pintype "passive"))
      (node (ref "DB9_MALE_CONN") (pin "5") (pinfunction "5_5") (pintype "passive"))
      (node (ref "FTDI") (pin "GND") (pinfunction "GND_GND") (pintype "bidirectional"))
      (node (ref "J1") (pin "GND") (pinfunction "GNDBREAK_GND") (pintype "bidirectional"))
      (node (ref "J1") (pin "P$4") (pinfunction "GND_P$4") (pintype "bidirectional"))
      (node (ref "PWR") (pin "C") (pinfunction "C_C") (pintype "passive"))
      (node (ref "Q1") (pin "2") (pinfunction "E_2") (pintype "passive"))
      (node (ref "R12") (pin "1") (pinfunction "1_1") (pintype "passive"))
      (node (ref "R2") (pin "1") (pinfunction "1_1") (pintype "passive"))
      (node (ref "R4") (pin "1") (pinfunction "1_1") (pintype "passive"))
      (node (ref "R7") (pin "1") (pinfunction "1_1") (pintype "passive"))
      (node (ref "R8") (pin "1") (pinfunction "1_1") (pintype "passive"))
      (node (ref "RJ45_IN") (pin "4") (pinfunction "4_4") (pintype "passive"))
      (node (ref "RJ45_IN") (pin "5") (pinfunction "5_5") (pintype "passive"))
      (node (ref "RJ45_OUT") (pin "4") (pinfunction "4_4") (pintype "passive"))
      (node (ref "RJ45_OUT") (pin "5") (pinfunction "5_5") (pintype "passive"))
      (node (ref "RSSI") (pin "C") (pinfunction "C_C") (pintype "passive"))
      (node (ref "RTS") (pin "C") (pinfunction "C_C") (pintype "passive"))
      (node (ref "S2") (pin "B2") (pinfunction "2_B2") (pintype "passive"))
      (node (ref "SOLAR") (pin "1") (pinfunction "1_1") (pintype "passive"))
      (node (ref "U1") (pin "2") (pinfunction "GND_2") (pintype "bidirectional"))
      (node (ref "U10") (pin "5") (pinfunction "GND_5") (pintype "bidirectional"))
      (node (ref "U11") (pin "4") (pinfunction "SD_4") (pintype "bidirectional"))
      (node (ref "U11") (pin "6") (pinfunction "GND_6") (pintype "bidirectional"))
      (node (ref "U2") (pin "2") (pinfunction "GND_2") (pintype "bidirectional"))
      (node (ref "U3") (pin "4") (pinfunction "VSS_4") (pintype "bidirectional"))
      (node (ref "U3") (pin "6") (pinfunction "~{CE}_6") (pintype "bidirectional"))
      (node (ref "U4") (pin "2") (pinfunction "GND_2") (pintype "input"))
      (node (ref "U5") (pin "2") (pinfunction "GND_2") (pintype "bidirectional"))
      (node (ref "U6") (pin "18") (pinfunction "GND18_18") (pintype "power_in"))
      (node (ref "U6") (pin "21") (pinfunction "GND21_21") (pintype "power_in"))
      (node (ref "U6") (pin "25") (pinfunction "AGND_25") (pintype "power_in"))
      (node (ref "U6") (pin "26") (pinfunction "TEST_26") (pintype "input"))
      (node (ref "U6") (pin "7") (pinfunction "GND7_7") (pintype "power_in"))
      (node (ref "U7") (pin "10") (pinfunction "GND_10") (pintype "power_in"))
      (node (ref "U8") (pin "15") (pinfunction "GND_15") (pintype "bidirectional"))
      (node (ref "U9") (pin "5") (pinfunction "VSS_5") (pintype "bidirectional"))
      (node (ref "USB_DN") (pin "C") (pinfunction "C_C") (pintype "passive"))
      (node (ref "USB_IN") (pin "GND") (pinfunction "GND_GND") (pintype "bidirectional"))
      (node (ref "USB_OUT") (pin "GND") (pinfunction "GND_GND") (pintype "bidirectional"))
      (node (ref "USB_PWR") (pin "C") (pinfunction "C_C") (pintype "passive"))
      (node (ref "XV_LT") (pin "1") (pinfunction "1_1") (pintype "passive"))
    )
    (net (code "18") (name "GPIO1") (class "Default")
      (node (ref "U7") (pin "9") (pinfunction "DTR_9") (pintype "bidirectional"))
      (node (ref "XV_LT") (pin "2") (pinfunction "2_2") (pintype "passive"))
    )
    (net (code "19") (name "GPIO2") (class "Default")
      (node (ref "U7") (pin "19") (pinfunction "DIO1_19") (pintype "bidirectional"))
      (node (ref "XV_RT") (pin "9") (pinfunction "9_9") (pintype "passive"))
    )
    (net (code "20") (name "GPIO3") (class "Default")
      (node (ref "U7") (pin "18") (pinfunction "DIO2_18") (pintype "bidirectional"))
      (node (ref "XV_RT") (pin "8") (pinfunction "8_8") (pintype "passive"))
    )
    (net (code "21") (name "GPIO4") (class "Default")
      (node (ref "U7") (pin "13") (pinfunction "DIO9_13") (pintype "bidirectional"))
      (node (ref "XV_RT") (pin "3") (pinfunction "3_3") (pintype "passive"))
    )
    (net (code "22") (name "GPIO6") (class "Default")
      (node (ref "U7") (pin "15") (pinfunction "DIO5_15") (pintype "bidirectional"))
      (node (ref "XV_RT") (pin "5") (pinfunction "5_5") (pintype "passive"))
    )
    (net (code "23") (name "GPIO7") (class "Default")
      (node (ref "U7") (pin "7") (pinfunction "DIO11_7") (pintype "bidirectional"))
      (node (ref "XV_LT") (pin "4") (pinfunction "4_4") (pintype "passive"))
    )
    (net (code "24") (name "GPIO8") (class "Default")
      (node (ref "U7") (pin "4") (pinfunction "DIO12_4") (pintype "bidirectional"))
      (node (ref "XV_LT") (pin "7") (pinfunction "7_7") (pintype "passive"))
    )
    (net (code "25") (name "GPIO9") (class "Default")
      (node (ref "U7") (pin "8") (pinfunction "RES_8") (pintype "bidirectional"))
      (node (ref "XV_LT") (pin "3") (pinfunction "3_3") (pintype "passive"))
    )
    (net (code "26") (name "GPIO14") (class "Default")
      (node (ref "U7") (pin "11") (pinfunction "DIO4_11") (pintype "bidirectional"))
      (node (ref "XV_RT") (pin "1") (pinfunction "1_1") (pintype "passive"))
    )
    (net (code "27") (name "Net-(BATT_SW_NO-P)") (class "Default")
      (node (ref "BATT_SW_NO") (pin "2") (pinfunction "P_2") (pintype "passive"))
      (node (ref "D4") (pin "C") (pinfunction "C_C") (pintype "passive"))
    )
    (net (code "28") (name "Net-(C1-+)") (class "Default")
      (node (ref "C1") (pin "A") (pinfunction "+_A") (pintype "passive"))
      (node (ref "SW_PWR") (pin "3") (pinfunction "S_3") (pintype "passive"))
      (node (ref "U1") (pin "1") (pinfunction "VI_1") (pintype "bidirectional"))
      (node (ref "U1") (pin "3") (pinfunction "EN_3") (pintype "bidirectional"))
    )
    (net (code "29") (name "Net-(C3-+)") (class "Default")
      (node (ref "C2") (pin "1") (pinfunction "1_1") (pintype "passive"))
      (node (ref "C3") (pin "A") (pinfunction "+_A") (pintype "passive"))
      (node (ref "D6") (pin "A") (pinfunction "A_A") (pintype "passive"))
      (node (ref "L1") (pin "2") (pinfunction "2_2") (pintype "passive"))
      (node (ref "R1") (pin "2") (pinfunction "2_2") (pintype "passive"))
    )
    (net (code "30") (name "Net-(C6-+)") (class "Default")
      (node (ref "C6") (pin "A") (pinfunction "+_A") (pintype "passive"))
      (node (ref "D3") (pin "A") (pinfunction "A_A") (pintype "passive"))
      (node (ref "FERRITE_BEAD2") (pin "2") (pinfunction "P$2_2") (pintype "bidirectional"))
      (node (ref "U2") (pin "6") (pinfunction "OUT_6") (pintype "bidirectional"))
    )
    (net (code "31") (name "Net-(CHG-PadC)") (class "Default")
      (node (ref "CHG") (pin "C") (pinfunction "C_C") (pintype "passive"))
      (node (ref "R7") (pin "2") (pinfunction "2_2") (pintype "passive"))
    )
    (net (code "32") (name "Net-(D1-PadA)") (class "Default")
      (node (ref "D1") (pin "A") (pinfunction "A_A") (pintype "passive"))
      (node (ref "F1") (pin "2") (pinfunction "2_2") (pintype "bidirectional"))
    )
    (net (code "33") (name "Net-(D4-PadA)") (class "Default")
      (node (ref "D4") (pin "A") (pinfunction "A_A") (pintype "passive"))
      (node (ref "F3") (pin "2") (pinfunction "2_2") (pintype "bidirectional"))
    )
    (net (code "34") (name "Net-(D5-PadA)") (class "Default")
      (node (ref "D5") (pin "A") (pinfunction "A_A") (pintype "passive"))
      (node (ref "F4") (pin "2") (pinfunction "2_2") (pintype "bidirectional"))
    )
    (net (code "35") (name "Net-(F2-Pad1)") (class "Default")
      (node (ref "F2") (pin "1") (pinfunction "1_1") (pintype "bidirectional"))
      (node (ref "USB_IN") (pin "VBUS") (pinfunction "VBUS_VBUS") (pintype "bidirectional"))
    )
    (net (code "36") (name "Net-(F4-Pad1)") (class "Default")
      (node (ref "F4") (pin "1") (pinfunction "1_1") (pintype "bidirectional"))
      (node (ref "SOLAR") (pin "2") (pinfunction "2_2") (pintype "passive"))
    )
    (net (code "37") (name "Net-(F5-Pad1)") (class "Default")
      (node (ref "F5") (pin "1") (pinfunction "1_1") (pintype "bidirectional"))
      (node (ref "FTDI") (pin "VBUS") (pinfunction "VBUS_VBUS") (pintype "bidirectional"))
    )
    (net (code "38") (name "Net-(FERRITE_BEAD-P$2)") (class "Default")
      (node (ref "F2") (pin "2") (pinfunction "2_2") (pintype "bidirectional"))
      (node (ref "FERRITE_BEAD") (pin "2") (pinfunction "P$2_2") (pintype "bidirectional"))
    )
    (net (code "39") (name "Net-(FERRITE_BEAD2-P$1)") (class "Default")
      (node (ref "FERRITE_BEAD2") (pin "1") (pinfunction "P$1_1") (pintype "bidirectional"))
      (node (ref "USB_OUT") (pin "VBUS") (pinfunction "VBUS_VBUS") (pintype "bidirectional"))
    )
    (net (code "40") (name "Net-(FERRITE_BEAD3-P$2)") (class "Default")
      (node (ref "F5") (pin "2") (pinfunction "2_2") (pintype "bidirectional"))
      (node (ref "FERRITE_BEAD3") (pin "2") (pinfunction "P$2_2") (pintype "bidirectional"))
    )
    (net (code "41") (name "Net-(J1-PWR)") (class "Default")
      (node (ref "F1") (pin "1") (pinfunction "1_1") (pintype "bidirectional"))
      (node (ref "J1") (pin "VIN0") (pinfunction "PWR_VIN0") (pintype "bidirectional"))
    )
    (net (code "42") (name "Net-(PWR-PadA)") (class "Default")
      (node (ref "PWR") (pin "A") (pinfunction "A_A") (pintype "passive"))
      (node (ref "R18") (pin "1") (pinfunction "1_1") (pintype "passive"))
    )
    (net (code "43") (name "Net-(Q1-B)") (class "Default")
      (node (ref "Q1") (pin "1") (pinfunction "B_1") (pintype "passive"))
      (node (ref "R5") (pin "1") (pinfunction "1_1") (pintype "passive"))
    )
    (net (code "44") (name "Net-(Q2-D)") (class "Default")
      (node (ref "C12") (pin "1") (pinfunction "1_1") (pintype "passive"))
      (node (ref "Q2") (pin "3") (pinfunction "D_3") (pintype "passive"))
      (node (ref "U3") (pin "7") (pinfunction "BAT_7") (pintype "bidirectional"))
      (node (ref "U3") (pin "8") (pinfunction "OUT_8") (pintype "bidirectional"))
    )
    (net (code "45") (name "Net-(R9-Pad1)") (class "Default")
      (node (ref "R9") (pin "1") (pinfunction "1_1") (pintype "passive"))
      (node (ref "TXD") (pin "A") (pinfunction "A_A") (pintype "passive"))
    )
    (net (code "46") (name "Net-(R10-Pad1)") (class "Default")
      (node (ref "R10") (pin "1") (pinfunction "1_1") (pintype "passive"))
      (node (ref "RXD") (pin "A") (pinfunction "A_A") (pintype "passive"))
    )
    (net (code "47") (name "Net-(R14-Pad1)") (class "Default")
      (node (ref "R14") (pin "1") (pinfunction "1_1") (pintype "passive"))
      (node (ref "RSSI") (pin "A") (pinfunction "A_A") (pintype "passive"))
    )
    (net (code "48") (name "Net-(R15-Pad2)") (class "Default")
      (node (ref "R15") (pin "2") (pinfunction "2_2") (pintype "passive"))
      (node (ref "RTS") (pin "A") (pinfunction "A_A") (pintype "passive"))
    )
    (net (code "49") (name "Net-(R17-Pad1)") (class "Default")
      (node (ref "R17") (pin "1") (pinfunction "1_1") (pintype "passive"))
      (node (ref "USB_PWR") (pin "A") (pinfunction "A_A") (pintype "passive"))
    )
    (net (code "50") (name "Net-(R19-Pad1)") (class "Default")
      (node (ref "R19") (pin "1") (pinfunction "1_1") (pintype "passive"))
      (node (ref "USB_DN") (pin "A") (pinfunction "A_A") (pintype "passive"))
    )
    (net (code "51") (name "Net-(U1-FB)") (class "Default")
      (node (ref "C2") (pin "2") (pinfunction "2_2") (pintype "passive"))
      (node (ref "C4") (pin "1") (pinfunction "1_1") (pintype "passive"))
      (node (ref "R1") (pin "1") (pinfunction "1_1") (pintype "passive"))
      (node (ref "R2") (pin "2") (pinfunction "2_2") (pintype "passive"))
      (node (ref "U1") (pin "4") (pinfunction "FB_4") (pintype "bidirectional"))
    )
    (net (code "52") (name "Net-(U1-SW)") (class "Default")
      (node (ref "L1") (pin "1") (pinfunction "1_1") (pintype "passive"))
      (node (ref "U1") (pin "5") (pinfunction "SW_5") (pintype "bidirectional"))
    )
    (net (code "53") (name "Net-(U2-EN)") (class "Default")
      (node (ref "R3") (pin "1") (pinfunction "1_1") (pintype "passive"))
      (node (ref "U2") (pin "3") (pinfunction "EN_3") (pintype "bidirectional"))
      (node (ref "U2") (pin "4") (pinfunction "~{FLAG}_4") (pintype "bidirectional"))
    )
    (net (code "54") (name "Net-(U2-ILIM)") (class "Default")
      (node (ref "R4") (pin "2") (pinfunction "2_2") (pintype "passive"))
      (node (ref "U2") (pin "5") (pinfunction "ILIM_5") (pintype "bidirectional"))
    )
    (net (code "55") (name "Net-(U3-STAT)") (class "Default")
      (node (ref "CHG") (pin "A") (pinfunction "A_A") (pintype "passive"))
      (node (ref "U3") (pin "3") (pinfunction "STAT_3") (pintype "bidirectional"))
    )
    (net (code "56") (name "Net-(U4-BP)") (class "Default")
      (node (ref "C19") (pin "1") (pinfunction "1_1") (pintype "passive"))
      (node (ref "U4") (pin "4") (pinfunction "BP_4") (pintype "input"))
    )
    (net (code "57") (name "Net-(U4-OUT)") (class "Default")
      (node (ref "C18") (pin "1") (pinfunction "1_1") (pintype "passive"))
      (node (ref "D14") (pin "A") (pinfunction "A_A") (pintype "passive"))
      (node (ref "U4") (pin "5") (pinfunction "OUT_5") (pintype "passive"))
    )
    (net (code "58") (name "Net-(U5-EN)") (class "Default")
      (node (ref "R11") (pin "2") (pinfunction "2_2") (pintype "passive"))
      (node (ref "U5") (pin "3") (pinfunction "EN_3") (pintype "bidirectional"))
      (node (ref "U5") (pin "4") (pinfunction "~{FLAG}_4") (pintype "bidirectional"))
    )
    (net (code "59") (name "Net-(U5-ILIM)") (class "Default")
      (node (ref "R12") (pin "2") (pinfunction "2_2") (pintype "passive"))
      (node (ref "U5") (pin "5") (pinfunction "ILIM_5") (pintype "bidirectional"))
    )
    (net (code "60") (name "Net-(U5-OUT)") (class "Default")
      (node (ref "C14") (pin "1") (pinfunction "1_1") (pintype "passive"))
      (node (ref "D9") (pin "A") (pinfunction "A_A") (pintype "passive"))
      (node (ref "U5") (pin "6") (pinfunction "OUT_6") (pintype "bidirectional"))
    )
    (net (code "61") (name "Net-(U6-RXLED)") (class "Default")
      (node (ref "RXD") (pin "C") (pinfunction "C_C") (pintype "passive"))
      (node (ref "U6") (pin "22") (pinfunction "RXLED_22") (pintype "input"))
    )
    (net (code "62") (name "Net-(U6-TXLED)") (class "Default")
      (node (ref "TXD") (pin "C") (pinfunction "C_C") (pintype "passive"))
      (node (ref "U6") (pin "23") (pinfunction "TXLED_23") (pintype "input"))
    )
    (net (code "63") (name "Net-(U6-USBDM)") (class "Default")
      (node (ref "FTDI") (pin "D-") (pinfunction "D-_D-") (pintype "bidirectional"))
      (node (ref "U6") (pin "16") (pinfunction "USBDM_16") (pintype "bidirectional"))
    )
    (net (code "64") (name "Net-(U6-USBDP)") (class "Default")
      (node (ref "FTDI") (pin "D+") (pinfunction "D+_D+") (pintype "bidirectional"))
      (node (ref "U6") (pin "15") (pinfunction "USBDP_15") (pintype "bidirectional"))
    )
    (net (code "65") (name "Net-(U7-RES-Pad14)") (class "Default")
      (node (ref "U7") (pin "14") (pinfunction "RES_14") (pintype "bidirectional"))
      (node (ref "XV_RT") (pin "4") (pinfunction "4_4") (pintype "passive"))
    )
    (net (code "66") (name "Net-(U8-C1+)") (class "Default")
      (node (ref "C7") (pin "1") (pinfunction "1_1") (pintype "passive"))
      (node (ref "U8") (pin "1") (pinfunction "C1+_1") (pintype "bidirectional"))
    )
    (net (code "67") (name "Net-(U8-C1-)") (class "Default")
      (node (ref "C7") (pin "2") (pinfunction "2_2") (pintype "passive"))
      (node (ref "U8") (pin "3") (pinfunction "C1-_3") (pintype "bidirectional"))
    )
    (net (code "68") (name "Net-(U8-C2+)") (class "Default")
      (node (ref "C8") (pin "1") (pinfunction "1_1") (pintype "passive"))
      (node (ref "U8") (pin "4") (pinfunction "C2+_4") (pintype "bidirectional"))
    )
    (net (code "69") (name "Net-(U8-C2-)") (class "Default")
      (node (ref "C8") (pin "2") (pinfunction "2_2") (pintype "passive"))
      (node (ref "U8") (pin "5") (pinfunction "C2-_5") (pintype "bidirectional"))
    )
    (net (code "70") (name "Net-(U8-V+)") (class "Default")
      (node (ref "C9") (pin "1") (pinfunction "1_1") (pintype "passive"))
      (node (ref "U8") (pin "2") (pinfunction "V+_2") (pintype "bidirectional"))
    )
    (net (code "71") (name "Net-(U8-V-)") (class "Default")
      (node (ref "C10") (pin "1") (pinfunction "1_1") (pintype "passive"))
      (node (ref "U8") (pin "6") (pinfunction "V-_6") (pintype "bidirectional"))
    )
    (net (code "72") (name "Net-(U9-OSC1)") (class "Default")
      (node (ref "C24") (pin "1") (pinfunction "1_1") (pintype "passive"))
      (node (ref "U9") (pin "16") (pinfunction "OSC1_16") (pintype "bidirectional"))
      (node (ref "Y1") (pin "1") (pinfunction "1_1") (pintype "passive"))
    )
    (net (code "73") (name "Net-(U9-OSC2)") (class "Default")
      (node (ref "C23") (pin "1") (pinfunction "1_1") (pintype "passive"))
      (node (ref "U9") (pin "15") (pinfunction "OSC2_15") (pintype "bidirectional"))
      (node (ref "Y1") (pin "3") (pinfunction "2_3") (pintype "passive"))
    )
    (net (code "74") (name "Net-(U11-VCC1)") (class "Default")
      (node (ref "C21") (pin "1") (pinfunction "1_1") (pintype "passive"))
      (node (ref "R20") (pin "1") (pinfunction "1_1") (pintype "passive"))
      (node (ref "U11") (pin "5") (pinfunction "VCC1_5") (pintype "bidirectional"))
    )
    (net (code "75") (name "Net-(U11-VCC2)") (class "Default")
      (node (ref "R21") (pin "2") (pinfunction "2_2") (pintype "passive"))
      (node (ref "U11") (pin "1") (pinfunction "VCC2_1") (pintype "bidirectional"))
    )
    (net (code "76") (name "OSCI") (class "Default")
      (node (ref "U6") (pin "27") (pinfunction "OSCI_27") (pintype "input"))
    )
    (net (code "77") (name "OSCO") (class "Default")
      (node (ref "U6") (pin "28") (pinfunction "OSCO_28") (pintype "output"))
    )
    (net (code "78") (name "PWREN") (class "Default")
      (node (ref "U6") (pin "14") (pinfunction "PWREN_14") (pintype "input"))
    )
    (net (code "79") (name "RESET") (class "Default")
      (node (ref "R13") (pin "2") (pinfunction "2_2") (pintype "passive"))
      (node (ref "S2") (pin "A2") (pinfunction "1_A2") (pintype "passive"))
      (node (ref "U6") (pin "19") (pinfunction "RESET_19") (pintype "input"))
      (node (ref "U7") (pin "5") (pinfunction "RESET_5") (pintype "input"))
      (node (ref "XV_LT") (pin "6") (pinfunction "6_6") (pintype "passive"))
    )
    (net (code "80") (name "RI") (class "Default")
      (node (ref "U6") (pin "6") (pinfunction "RI_6") (pintype "input"))
      (node (ref "U9") (pin "9") (pinfunction "RI_9") (pintype "bidirectional"))
    )
    (net (code "81") (name "RS232_CTS") (class "Default")
      (node (ref "DB9_MALE_CONN") (pin "8") (pinfunction "8_8") (pintype "passive"))
      (node (ref "U8") (pin "7") (pinfunction "T2OUT_7") (pintype "output"))
    )
    (net (code "82") (name "RS232_DTR") (class "Default")
      (node (ref "DB9_MALE_CONN") (pin "4") (pinfunction "4_4") (pintype "passive"))
      (node (ref "R5") (pin "2") (pinfunction "2_2") (pintype "passive"))
    )
    (net (code "83") (name "RS232_RTS") (class "Default")
      (node (ref "DB9_MALE_CONN") (pin "7") (pinfunction "7_7") (pintype "passive"))
      (node (ref "U8") (pin "8") (pinfunction "R2IN_8") (pintype "input"))
    )
    (net (code "84") (name "RS232_RX") (class "Default")
      (node (ref "DB9_MALE_CONN") (pin "3") (pinfunction "3_3") (pintype "passive"))
      (node (ref "U8") (pin "13") (pinfunction "R1IN_13") (pintype "input"))
    )
    (net (code "85") (name "RS232_TX") (class "Default")
      (node (ref "DB9_MALE_CONN") (pin "2") (pinfunction "2_2") (pintype "passive"))
      (node (ref "U8") (pin "14") (pinfunction "T1OUT_14") (pintype "output"))
    )
    (net (code "86") (name "RSSI") (class "Default")
      (node (ref "R14") (pin "2") (pinfunction "2_2") (pintype "passive"))
      (node (ref "U7") (pin "6") (pinfunction "RSSI_6") (pintype "bidirectional"))
      (node (ref "XV_LT") (pin "5") (pinfunction "5_5") (pintype "passive"))
    )
    (net (code "87") (name "RTS") (class "Default")
      (node (ref "R15") (pin "1") (pinfunction "1_1") (pintype "passive"))
      (node (ref "U6") (pin "3") (pinfunction "RTS_3") (pintype "output"))
      (node (ref "U7") (pin "12") (pinfunction "CTS_12") (pintype "output"))
      (node (ref "U8") (pin "9") (pinfunction "R2OUT_9") (pintype "output"))
      (node (ref "U9") (pin "13") (pinfunction "RTS_13") (pintype "bidirectional"))
      (node (ref "XV_RT") (pin "2") (pinfunction "2_2") (pintype "passive"))
    )
    (net (code "88") (name "RXIR") (class "Default")
      (node (ref "U11") (pin "3") (pinfunction "RXD_3") (pintype "bidirectional"))
      (node (ref "U9") (pin "3") (pinfunction "RXIR_3") (pintype "bidirectional"))
    )
    (net (code "89") (name "SEN2") (class "Default")
      (node (ref "U7") (pin "20") (pinfunction "DIO0_20") (pintype "bidirectional"))
      (node (ref "XV_RT") (pin "10") (pinfunction "10_10") (pintype "passive"))
    )
    (net (code "90") (name "SENSOR5") (class "Default")
      (node (ref "U7") (pin "17") (pinfunction "DIO3_17") (pintype "bidirectional"))
      (node (ref "XV_RT") (pin "7") (pinfunction "7_7") (pintype "passive"))
    )
    (net (code "91") (name "SLEEP") (class "Default")
      (node (ref "U6") (pin "12") (pinfunction "SLEEP_12") (pintype "input"))
    )
    (net (code "92") (name "TXDEN") (class "Default")
      (node (ref "U10") (pin "2") (pinfunction "/RE_2") (pintype "bidirectional"))
      (node (ref "U10") (pin "3") (pinfunction "DE_3") (pintype "bidirectional"))
      (node (ref "U6") (pin "13") (pinfunction "TXDEN_13") (pintype "input"))
    )
    (net (code "93") (name "TXIR") (class "Default")
      (node (ref "U11") (pin "2") (pinfunction "TXD_2") (pintype "bidirectional"))
      (node (ref "U9") (pin "2") (pinfunction "TXIR_2") (pintype "bidirectional"))
    )
    (net (code "94") (name "VCC") (class "Default")
      (node (ref "C16") (pin "1") (pinfunction "1_1") (pintype "passive"))
      (node (ref "D13") (pin "C") (pinfunction "C_C") (pintype "passive"))
      (node (ref "D14") (pin "C") (pinfunction "C_C") (pintype "passive"))
      (node (ref "R10") (pin "2") (pinfunction "2_2") (pintype "passive"))
      (node (ref "R17") (pin "2") (pinfunction "2_2") (pintype "passive"))
      (node (ref "R9") (pin "2") (pinfunction "2_2") (pintype "passive"))
      (node (ref "U10") (pin "8") (pinfunction "VCC_8") (pintype "bidirectional"))
    )
    (net (code "95") (name "VIN") (class "Default")
      (node (ref "C11") (pin "1") (pinfunction "1_1") (pintype "passive"))
      (node (ref "C17") (pin "1") (pinfunction "1_1") (pintype "passive"))
      (node (ref "D1") (pin "C") (pinfunction "C_C") (pintype "passive"))
      (node (ref "D3") (pin "C") (pinfunction "C_C") (pintype "passive"))
      (node (ref "D5") (pin "C") (pinfunction "C_C") (pintype "passive"))
      (node (ref "D9") (pin "C") (pinfunction "C_C") (pintype "passive"))
      (node (ref "Q2") (pin "1") (pinfunction "G_1") (pintype "passive"))
      (node (ref "R8") (pin "2") (pinfunction "2_2") (pintype "passive"))
      (node (ref "SW_PWR") (pin "2") (pinfunction "P_2") (pintype "passive"))
      (node (ref "U3") (pin "1") (pinfunction "IN_1") (pintype "bidirectional"))
      (node (ref "U3") (pin "2") (pinfunction "VCC_2") (pintype "bidirectional"))
      (node (ref "U4") (pin "1") (pinfunction "IN_1") (pintype "input"))
      (node (ref "U4") (pin "3") (pinfunction "EN_3") (pintype "input"))
    )
    (net (code "96") (name "V_BAT") (class "Default")
      (node (ref "BATT") (pin "2") (pinfunction "2_2") (pintype "passive"))
      (node (ref "F3") (pin "1") (pinfunction "1_1") (pintype "bidirectional"))
      (node (ref "Q2") (pin "2") (pinfunction "S_2") (pintype "passive"))
    )
    (net (code "97") (name "V_USB_DOWN") (class "Default")
      (node (ref "FERRITE_BEAD") (pin "1") (pinfunction "P$1_1") (pintype "bidirectional"))
      (node (ref "R19") (pin "2") (pinfunction "2_2") (pintype "passive"))
      (node (ref "R3") (pin "2") (pinfunction "2_2") (pintype "passive"))
      (node (ref "U2") (pin "1") (pinfunction "IN_1") (pintype "bidirectional"))
    )
    (net (code "98") (name "unconnected-(BATT_SW_NO-O-Pad1)") (class "Default")
      (node (ref "BATT_SW_NO") (pin "1") (pinfunction "O_1") (pintype "passive"))
    )
    (net (code "99") (name "unconnected-(DB9_MALE_CONN-Pad1)") (class "Default")
      (node (ref "DB9_MALE_CONN") (pin "1") (pinfunction "1_1") (pintype "passive"))
    )
    (net (code "100") (name "unconnected-(DB9_MALE_CONN-Pad6)") (class "Default")
      (node (ref "DB9_MALE_CONN") (pin "6") (pinfunction "6_6") (pintype "passive"))
    )
    (net (code "101") (name "unconnected-(DB9_MALE_CONN-Pad9)") (class "Default")
      (node (ref "DB9_MALE_CONN") (pin "9") (pinfunction "9_9") (pintype "passive"))
    )
    (net (code "102") (name "unconnected-(FTDI-MTN1-PadMTN3)") (class "Default")
      (node (ref "FTDI") (pin "MTN3") (pinfunction "MTN1_MTN3") (pintype "bidirectional"))
    )
    (net (code "103") (name "unconnected-(FTDI-MTN2-PadMTN1)") (class "Default")
      (node (ref "FTDI") (pin "MTN1") (pinfunction "MTN2_MTN1") (pintype "bidirectional"))
    )
    (net (code "104") (name "unconnected-(FTDI-MTN3-PadMTN2)") (class "Default")
      (node (ref "FTDI") (pin "MTN2") (pinfunction "MTN3_MTN2") (pintype "bidirectional"))
    )
    (net (code "105") (name "unconnected-(FTDI-PadID)") (class "Default")
      (node (ref "FTDI") (pin "ID") (pinfunction "ID_ID") (pintype "bidirectional"))
    )
    (net (code "106") (name "unconnected-(FTDI-PadMTN4)") (class "Default")
      (node (ref "FTDI") (pin "MTN4") (pinfunction "MTN4_MTN4") (pintype "bidirectional"))
    )
    (net (code "107") (name "unconnected-(JP4-Pad3)") (class "Default")
      (node (ref "JP4") (pin "3") (pinfunction "3_3") (pintype "passive"))
    )
    (net (code "108") (name "unconnected-(PCB-MTH1-Pad1)") (class "Default")
      (node (ref "PCB") (pin "1") (pinfunction "MTH1_1") (pintype "bidirectional"))
    )
    (net (code "109") (name "unconnected-(PCB-MTH2-Pad2)") (class "Default")
      (node (ref "PCB") (pin "2") (pinfunction "MTH2_2") (pintype "bidirectional"))
    )
    (net (code "110") (name "unconnected-(PCB-MTH3-Pad3)") (class "Default")
      (node (ref "PCB") (pin "3") (pinfunction "MTH3_3") (pintype "bidirectional"))
    )
    (net (code "111") (name "unconnected-(PCB-MTH4-Pad4)") (class "Default")
      (node (ref "PCB") (pin "4") (pinfunction "MTH4_4") (pintype "bidirectional"))
    )
    (net (code "112") (name "unconnected-(PCB-MTH5-Pad5)") (class "Default")
      (node (ref "PCB") (pin "5") (pinfunction "MTH5_5") (pintype "bidirectional"))
    )
    (net (code "113") (name "unconnected-(PCB-MTH6-Pad6)") (class "Default")
      (node (ref "PCB") (pin "6") (pinfunction "MTH6_6") (pintype "bidirectional"))
    )
    (net (code "114") (name "unconnected-(RJ45_IN-Pad2)") (class "Default")
      (node (ref "RJ45_IN") (pin "2") (pinfunction "2_2") (pintype "passive"))
    )
    (net (code "115") (name "unconnected-(RJ45_IN-Pad7)") (class "Default")
      (node (ref "RJ45_IN") (pin "7") (pinfunction "7_7") (pintype "passive"))
    )
    (net (code "116") (name "unconnected-(RJ45_IN-S-PadS1)") (class "Default")
      (node (ref "RJ45_IN") (pin "S1") (pinfunction "S_S1") (pintype "passive"))
    )
    (net (code "117") (name "unconnected-(RJ45_IN-S-PadS2)") (class "Default")
      (node (ref "RJ45_IN") (pin "S2") (pinfunction "S_S2") (pintype "passive"))
    )
    (net (code "118") (name "unconnected-(RJ45_IN-S-PadS3)") (class "Default")
      (node (ref "RJ45_IN") (pin "S3") (pinfunction "S_S3") (pintype "passive"))
    )
    (net (code "119") (name "unconnected-(RJ45_IN-S-PadS4)") (class "Default")
      (node (ref "RJ45_IN") (pin "S4") (pinfunction "S_S4") (pintype "passive"))
    )
    (net (code "120") (name "unconnected-(RJ45_OUT-Pad2)") (class "Default")
      (node (ref "RJ45_OUT") (pin "2") (pinfunction "2_2") (pintype "passive"))
    )
    (net (code "121") (name "unconnected-(RJ45_OUT-Pad7)") (class "Default")
      (node (ref "RJ45_OUT") (pin "7") (pinfunction "7_7") (pintype "passive"))
    )
    (net (code "122") (name "unconnected-(RJ45_OUT-S-PadS1)") (class "Default")
      (node (ref "RJ45_OUT") (pin "S1") (pinfunction "S_S1") (pintype "passive"))
    )
    (net (code "123") (name "unconnected-(RJ45_OUT-S-PadS2)") (class "Default")
      (node (ref "RJ45_OUT") (pin "S2") (pinfunction "S_S2") (pintype "passive"))
    )
    (net (code "124") (name "unconnected-(RJ45_OUT-S-PadS3)") (class "Default")
      (node (ref "RJ45_OUT") (pin "S3") (pinfunction "S_S3") (pintype "passive"))
    )
    (net (code "125") (name "unconnected-(RJ45_OUT-S-PadS4)") (class "Default")
      (node (ref "RJ45_OUT") (pin "S4") (pinfunction "S_S4") (pintype "passive"))
    )
    (net (code "126") (name "unconnected-(SW_PWR-O-Pad1)") (class "Default")
      (node (ref "SW_PWR") (pin "1") (pinfunction "O_1") (pintype "passive"))
    )
    (net (code "127") (name "unconnected-(U3-NC-Pad5)") (class "Default")
      (node (ref "U3") (pin "5") (pinfunction "NC_5") (pintype "bidirectional"))
    )
    (net (code "128") (name "unconnected-(U9-~{RESET}-Pad4)") (class "Default")
      (node (ref "U9") (pin "4") (pinfunction "~{RESET}_4") (pintype "bidirectional"))
    )
    (net (code "129") (name "unconnected-(USB_IN-MTN1-PadMTN3)") (class "Default")
      (node (ref "USB_IN") (pin "MTN3") (pinfunction "MTN1_MTN3") (pintype "bidirectional"))
    )
    (net (code "130") (name "unconnected-(USB_IN-MTN2-PadMTN1)") (class "Default")
      (node (ref "USB_IN") (pin "MTN1") (pinfunction "MTN2_MTN1") (pintype "bidirectional"))
    )
    (net (code "131") (name "unconnected-(USB_IN-MTN3-PadMTN2)") (class "Default")
      (node (ref "USB_IN") (pin "MTN2") (pinfunction "MTN3_MTN2") (pintype "bidirectional"))
    )
    (net (code "132") (name "unconnected-(USB_IN-PadID)") (class "Default")
      (node (ref "USB_IN") (pin "ID") (pinfunction "ID_ID") (pintype "bidirectional"))
    )
    (net (code "133") (name "unconnected-(USB_IN-PadMTN4)") (class "Default")
      (node (ref "USB_IN") (pin "MTN4") (pinfunction "MTN4_MTN4") (pintype "bidirectional"))
    )
    (net (code "134") (name "unconnected-(XV_LT-Pad11)") (class "Default")
      (node (ref "XV_LT") (pin "11") (pinfunction "11_11") (pintype "passive"))
    )
    (net (code "135") (name "unconnected-(XV_RT-Pad11)") (class "Default")
      (node (ref "XV_RT") (pin "11") (pinfunction "11_11") (pintype "passive"))
    )
  )
)
